# ewheel32.net
KiCad netlist of a schematic drawn in EAGLE
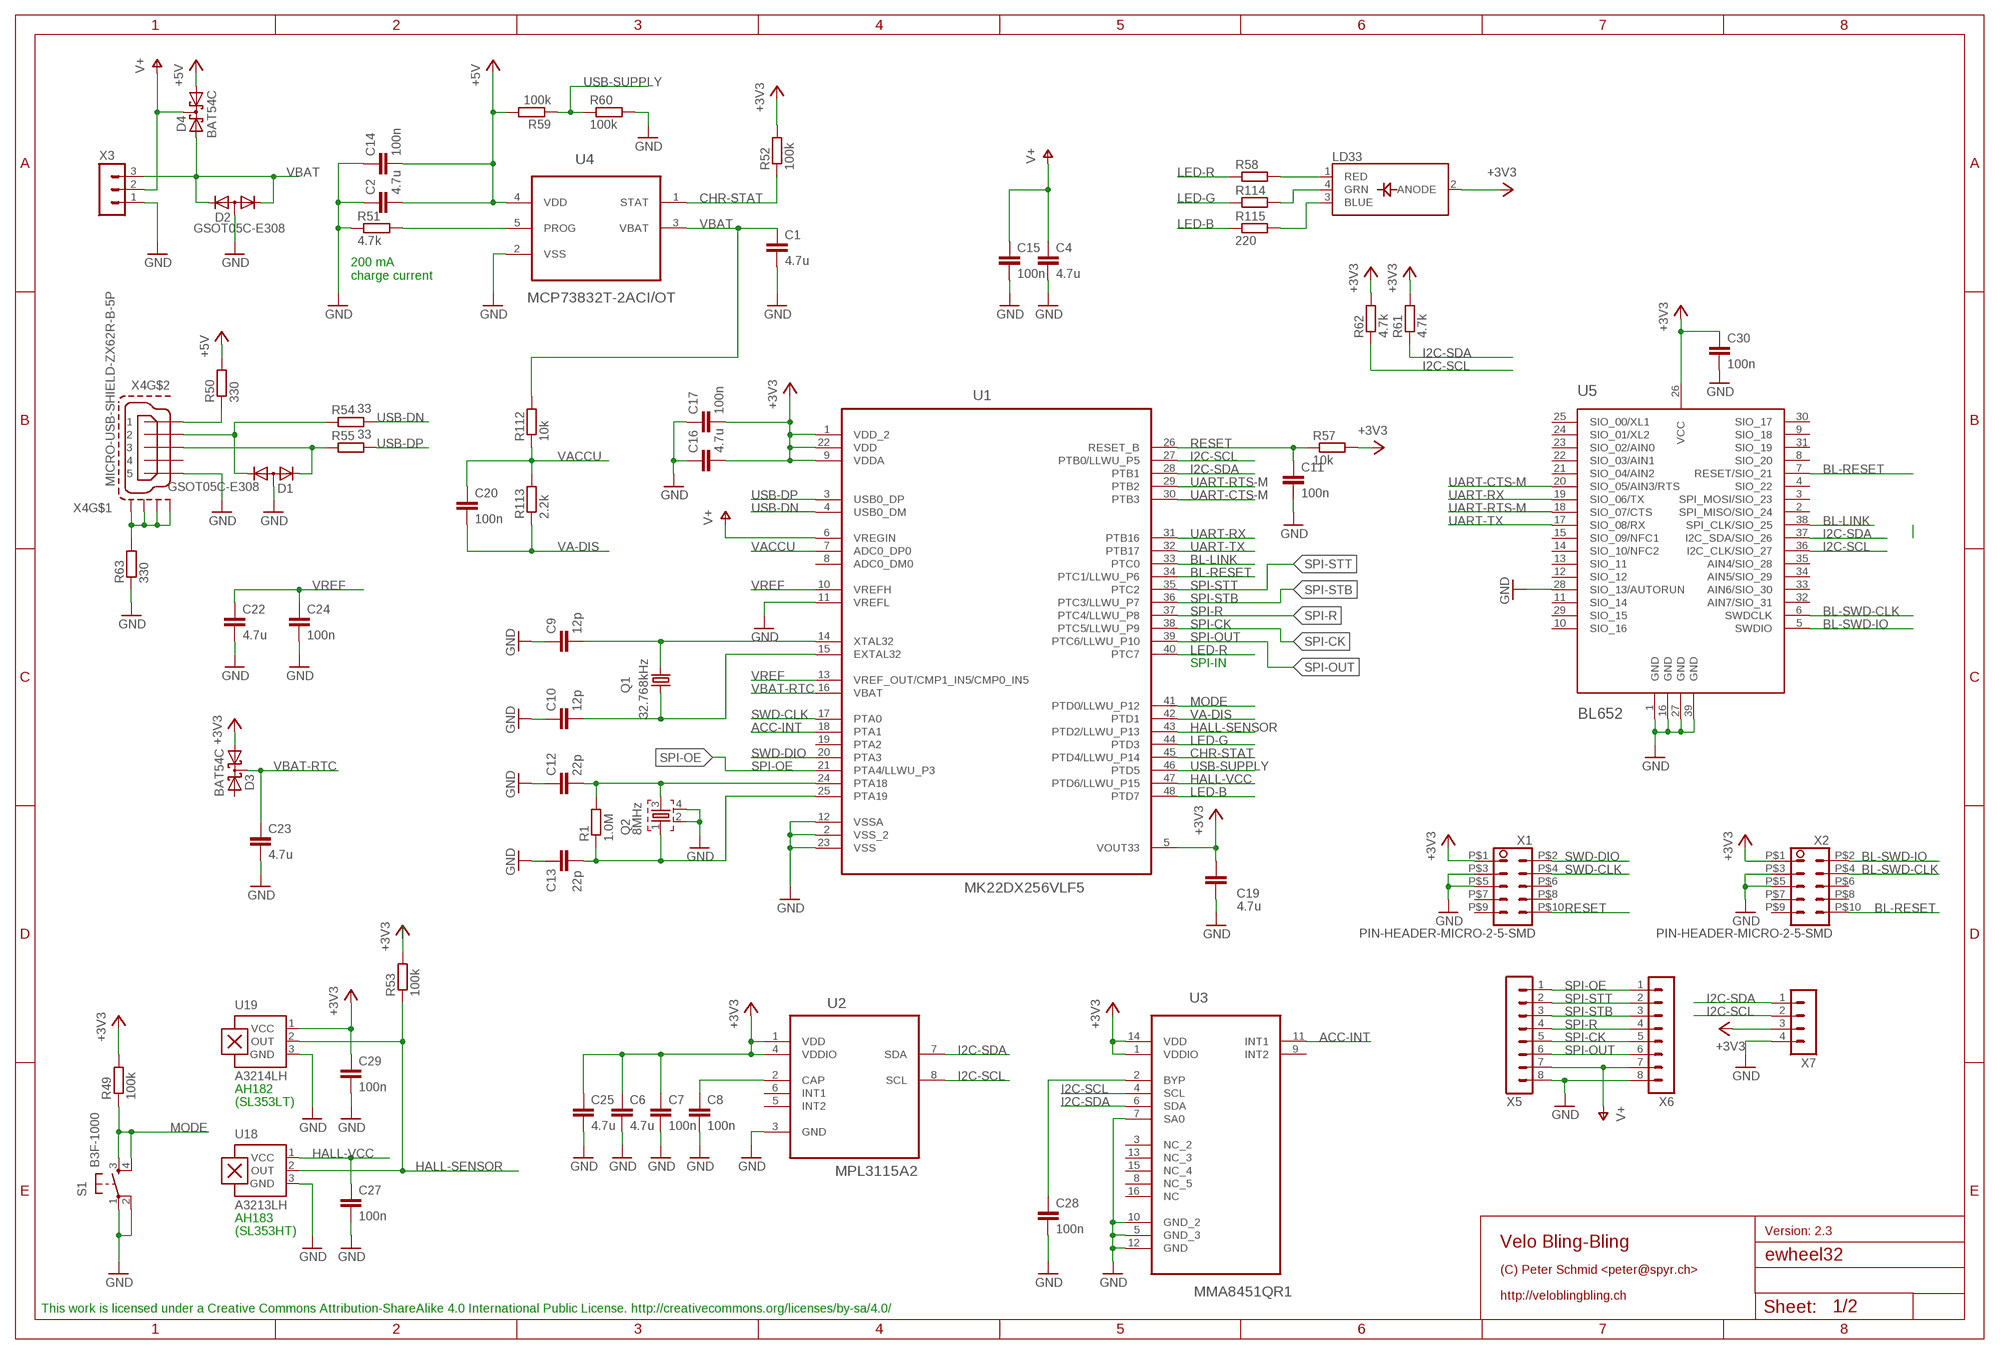
[diagram p0: schematic, sheet 1]
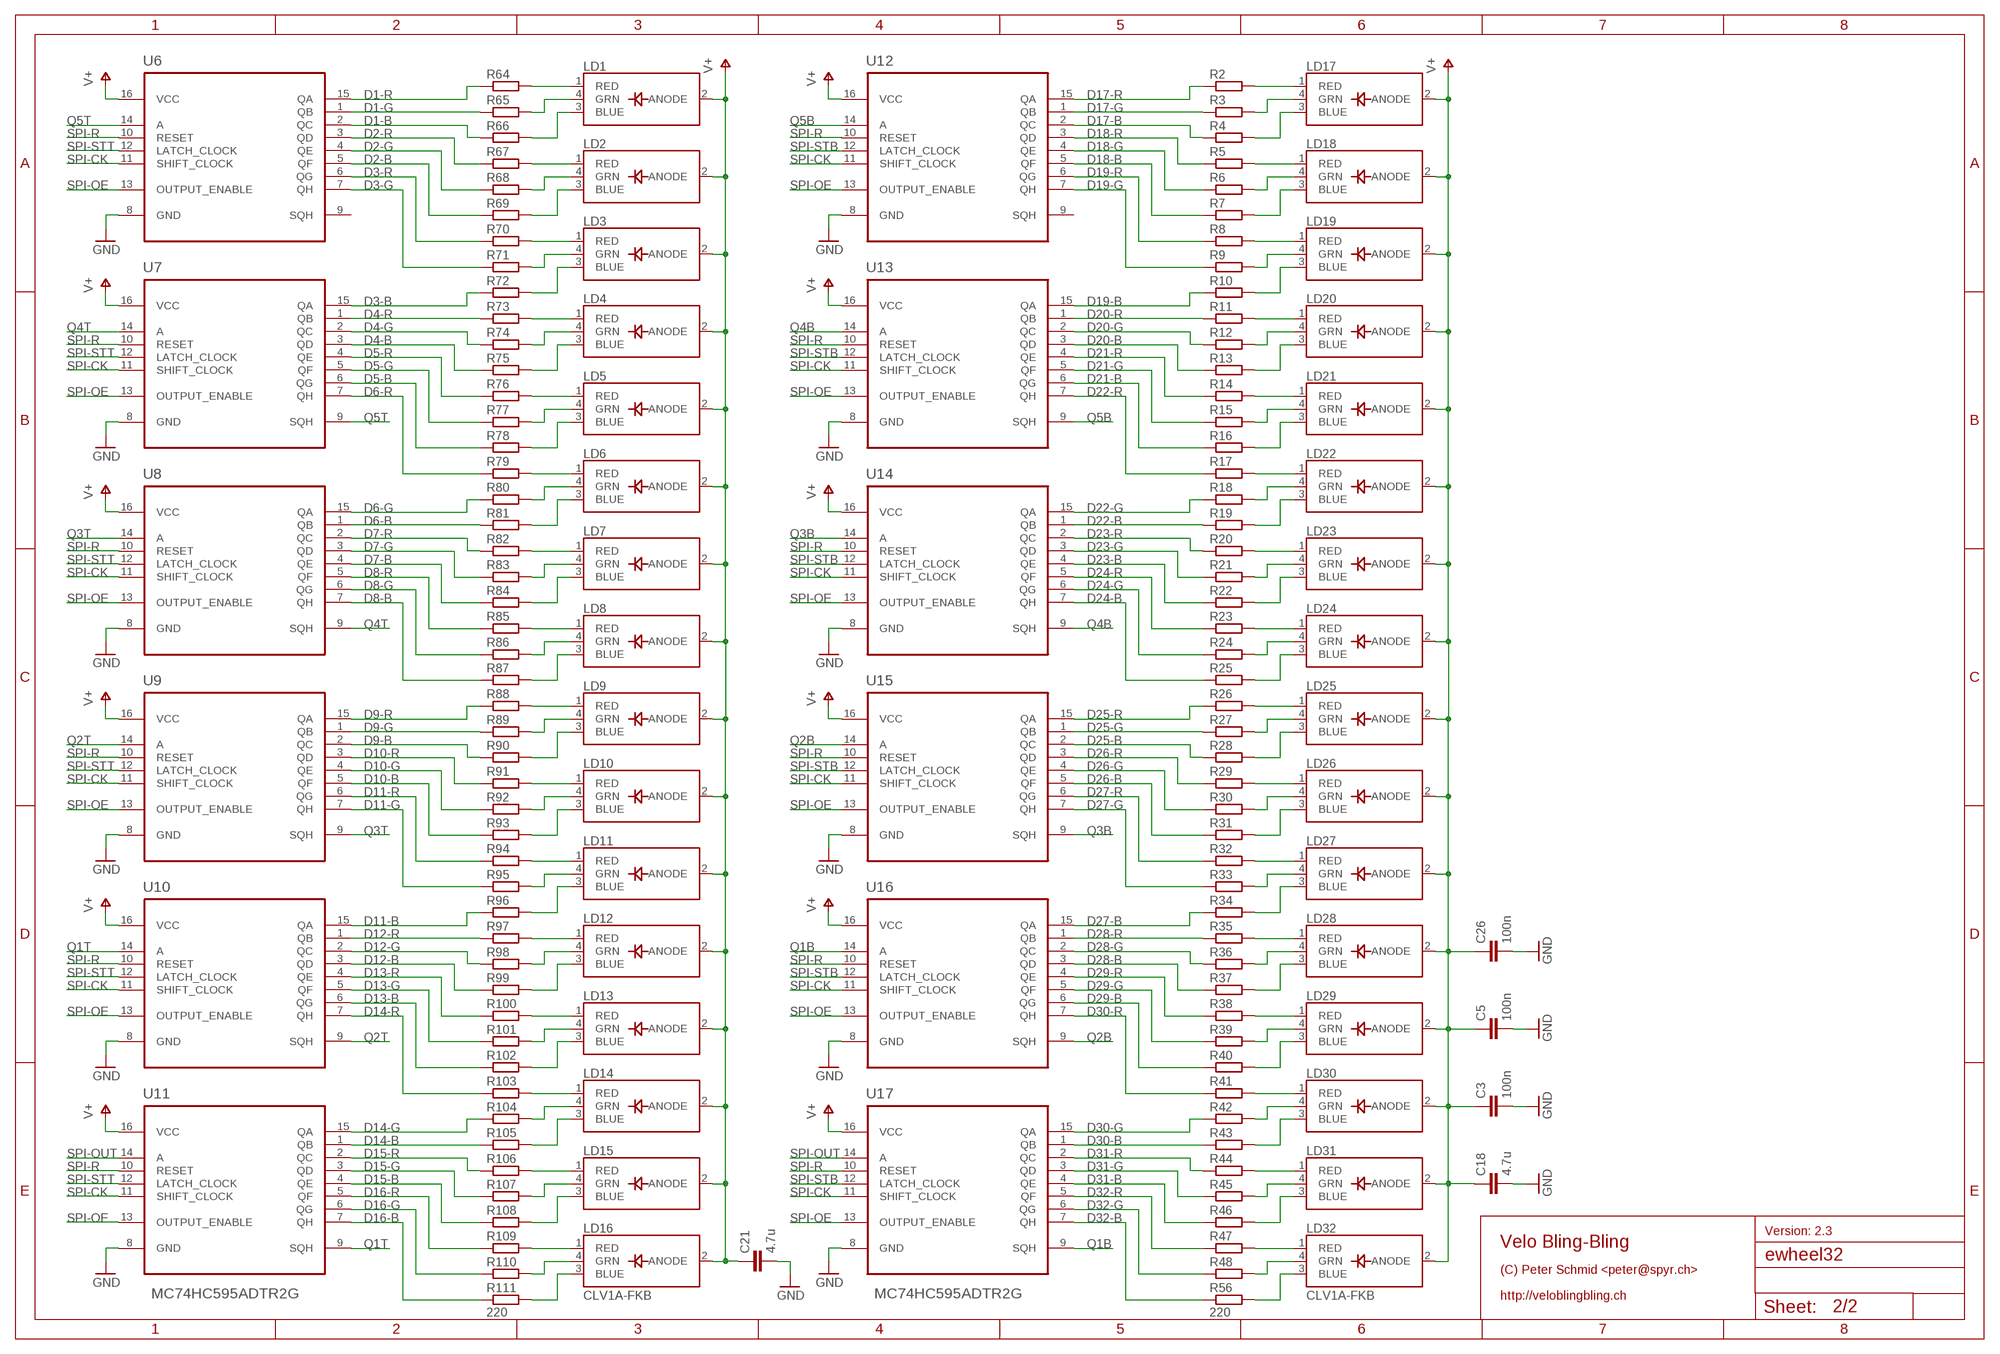
[diagram p1: schematic, sheet 2]

(export (version "E")
  (design (tool "Eeschema 10.0.6"))
  (components
    (comp (ref "C1")
      (value "4.7u")
      (footprint "eagle-import:C0805")
      (libsource (lib "eagle-import") (part "C-EUC0805"))
    )
    (comp (ref "C2")
      (value "4.7u")
      (footprint "eagle-import:C0805")
      (libsource (lib "eagle-import") (part "C-EUC0805"))
    )
    (comp (ref "C4")
      (value "4.7u")
      (footprint "eagle-import:C0805")
      (libsource (lib "eagle-import") (part "C-EUC0805"))
    )
    (comp (ref "C6")
      (value "4.7u")
      (footprint "eagle-import:C0805")
      (libsource (lib "eagle-import") (part "C-EUC0805"))
    )
    (comp (ref "C7")
      (value "100n")
      (footprint "eagle-import:C0805")
      (libsource (lib "eagle-import") (part "C-EUC0805"))
    )
    (comp (ref "C8")
      (value "100n")
      (footprint "eagle-import:C0805")
      (libsource (lib "eagle-import") (part "C-EUC0805"))
    )
    (comp (ref "C9")
      (value "12p")
      (footprint "eagle-import:C0805")
      (libsource (lib "eagle-import") (part "C-EUC0805"))
    )
    (comp (ref "C10")
      (value "12p")
      (footprint "eagle-import:C0805")
      (libsource (lib "eagle-import") (part "C-EUC0805"))
    )
    (comp (ref "C11")
      (value "100n")
      (footprint "eagle-import:C0805")
      (libsource (lib "eagle-import") (part "C-EUC0805"))
    )
    (comp (ref "C12")
      (value "22p")
      (footprint "eagle-import:C0805")
      (libsource (lib "eagle-import") (part "C-EUC0805"))
    )
    (comp (ref "C13")
      (value "22p")
      (footprint "eagle-import:C0805")
      (libsource (lib "eagle-import") (part "C-EUC0805"))
    )
    (comp (ref "C14")
      (value "100n")
      (footprint "eagle-import:C0805")
      (libsource (lib "eagle-import") (part "C-EUC0805"))
    )
    (comp (ref "C15")
      (value "100n")
      (footprint "eagle-import:C0805")
      (libsource (lib "eagle-import") (part "C-EUC0805"))
    )
    (comp (ref "C16")
      (value "4.7u")
      (footprint "eagle-import:C0805")
      (libsource (lib "eagle-import") (part "C-EUC0805"))
    )
    (comp (ref "C17")
      (value "100n")
      (footprint "eagle-import:C0805")
      (libsource (lib "eagle-import") (part "C-EUC0805"))
    )
    (comp (ref "C19")
      (value "4.7u")
      (footprint "eagle-import:C0805")
      (libsource (lib "eagle-import") (part "C-EUC0805"))
    )
    (comp (ref "C20")
      (value "100n")
      (footprint "eagle-import:C0805")
      (libsource (lib "eagle-import") (part "C-EUC0805"))
    )
    (comp (ref "C22")
      (value "4.7u")
      (footprint "eagle-import:C0805")
      (libsource (lib "eagle-import") (part "C-EUC0805"))
    )
    (comp (ref "C23")
      (value "4.7u")
      (footprint "eagle-import:C0805")
      (libsource (lib "eagle-import") (part "C-EUC0805"))
    )
    (comp (ref "C24")
      (value "100n")
      (footprint "eagle-import:C0805")
      (libsource (lib "eagle-import") (part "C-EUC0805"))
    )
    (comp (ref "C25")
      (value "4.7u")
      (footprint "eagle-import:C0805")
      (libsource (lib "eagle-import") (part "C-EUC0805"))
    )
    (comp (ref "C27")
      (value "100n")
      (footprint "eagle-import:C0805")
      (libsource (lib "eagle-import") (part "C-EUC0805"))
    )
    (comp (ref "C28")
      (value "100n")
      (footprint "eagle-import:C0805")
      (libsource (lib "eagle-import") (part "C-EUC0805"))
    )
    (comp (ref "C29")
      (value "100n")
      (footprint "eagle-import:C0805")
      (libsource (lib "eagle-import") (part "C-EUC0805"))
    )
    (comp (ref "C30")
      (value "100n")
      (footprint "eagle-import:C0805")
      (libsource (lib "eagle-import") (part "C-EUC0805"))
    )
    (comp (ref "D1")
      (value "GSOT05C-E308")
      (footprint "eagle-import:SOT23")
      (libsource (lib "eagle-import") (part "DIODE-2CA|ACSOT23"))
    )
    (comp (ref "D2")
      (value "GSOT05C-E308")
      (footprint "eagle-import:SOT23")
      (libsource (lib "eagle-import") (part "DIODE-2CA|ACSOT23"))
    )
    (comp (ref "D3")
      (value "BAT54C")
      (footprint "eagle-import:SOT23")
      (libsource (lib "eagle-import") (part "BAT54C"))
    )
    (comp (ref "D4")
      (value "BAT54C")
      (footprint "eagle-import:SOT23")
      (libsource (lib "eagle-import") (part "BAT54C"))
    )
    (comp (ref "LD33")
      (value "CLV1A-FKB")
      (footprint "eagle-import:RGBLED-PLCC4")
      (libsource (lib "eagle-import") (part "LED-RGB"))
    )
    (comp (ref "Q1")
      (value "32.768kHz")
      (footprint "eagle-import:ABS07")
      (libsource (lib "eagle-import") (part "ABS07"))
    )
    (comp (ref "Q2")
      (value "8MHz")
      (footprint "eagle-import:ABM3B")
      (libsource (lib "eagle-import") (part "ABM3B"))
    )
    (comp (ref "R1")
      (value "1.0M")
      (footprint "eagle-import:R0805")
      (libsource (lib "eagle-import") (part "R-EU_R0805"))
    )
    (comp (ref "R49")
      (value "100k")
      (footprint "eagle-import:R0805")
      (libsource (lib "eagle-import") (part "R-EU_R0805"))
    )
    (comp (ref "R50")
      (value "330")
      (footprint "eagle-import:R1206")
      (libsource (lib "eagle-import") (part "R-EU_R1206"))
    )
    (comp (ref "R51")
      (value "4.7k")
      (footprint "eagle-import:R0805")
      (libsource (lib "eagle-import") (part "R-EU_R0805"))
    )
    (comp (ref "R52")
      (value "100k")
      (footprint "eagle-import:R0805")
      (libsource (lib "eagle-import") (part "R-EU_R0805"))
    )
    (comp (ref "R53")
      (value "100k")
      (footprint "eagle-import:R0805")
      (libsource (lib "eagle-import") (part "R-EU_R0805"))
    )
    (comp (ref "R54")
      (value "33")
      (footprint "eagle-import:R0805")
      (libsource (lib "eagle-import") (part "R-EU_R0805"))
    )
    (comp (ref "R55")
      (value "33")
      (footprint "eagle-import:R0805")
      (libsource (lib "eagle-import") (part "R-EU_R0805"))
    )
    (comp (ref "R57")
      (value "10k")
      (footprint "eagle-import:R0805")
      (libsource (lib "eagle-import") (part "R-EU_R0805"))
    )
    (comp (ref "R58")
      (value "220")
      (footprint "eagle-import:R0805")
      (libsource (lib "eagle-import") (part "R-EU_R0805"))
    )
    (comp (ref "R59")
      (value "100k")
      (footprint "eagle-import:R0805")
      (libsource (lib "eagle-import") (part "R-EU_R0805"))
    )
    (comp (ref "R60")
      (value "100k")
      (footprint "eagle-import:R0805")
      (libsource (lib "eagle-import") (part "R-EU_R0805"))
    )
    (comp (ref "R61")
      (value "4.7k")
      (footprint "eagle-import:R0805")
      (libsource (lib "eagle-import") (part "R-EU_R0805"))
    )
    (comp (ref "R62")
      (value "4.7k")
      (footprint "eagle-import:R0805")
      (libsource (lib "eagle-import") (part "R-EU_R0805"))
    )
    (comp (ref "R63")
      (value "330")
      (footprint "eagle-import:R1206")
      (libsource (lib "eagle-import") (part "R-EU_R1206"))
    )
    (comp (ref "R112")
      (value "10k")
      (footprint "eagle-import:R0805")
      (libsource (lib "eagle-import") (part "R-EU_R0805"))
    )
    (comp (ref "R113")
      (value "2.2k")
      (footprint "eagle-import:R0805")
      (libsource (lib "eagle-import") (part "R-EU_R0805"))
    )
    (comp (ref "R114")
      (value "220")
      (footprint "eagle-import:R0805")
      (libsource (lib "eagle-import") (part "R-EU_R0805"))
    )
    (comp (ref "R115")
      (value "220")
      (footprint "eagle-import:R0805")
      (libsource (lib "eagle-import") (part "R-EU_R0805"))
    )
    (comp (ref "S1")
      (value "B3F-1000")
      (footprint "eagle-import:B3S-1000")
      (libsource (lib "eagle-import") (part "B3S-1000"))
    )
    (comp (ref "U1")
      (value "MK22DX256VLF5")
      (footprint "eagle-import:QFP50P900X900X160-48N")
      (fields (field (name "MPN") "MK20DX128VLF5"))
      (libsource (lib "eagle-import") (part "MK20DX128VLF5"))
    )
    (comp (ref "U2")
      (value "MPL3115A2")
      (footprint "eagle-import:DFN300X500X120-8N")
      (libsource (lib "eagle-import") (part "MPL3115A2"))
    )
    (comp (ref "U3")
      (value "MMA8451QR1")
      (footprint "eagle-import:QFN50P300X300X100-16N")
      (libsource (lib "eagle-import") (part "MMA8451QR1"))
    )
    (comp (ref "U4")
      (value "MCP73832T-2ACI/OT")
      (footprint "eagle-import:SOT95P280X145-5N")
      (fields (field (name "MPN") "MCP73831T-2ACI/OT"))
      (libsource (lib "eagle-import") (part "MCP73831T-2ACI/OT"))
    )
    (comp (ref "U5")
      (value "BL652")
      (footprint "eagle-import:BL652")
      (libsource (lib "eagle-import") (part "LAIRD_BL652"))
    )
    (comp (ref "U18")
      (value "A3213LH")
      (footprint "eagle-import:SOT23-W")
      (fields (field (name "MPN") "A1381LLHLT-T"))
      (libsource (lib "eagle-import") (part "A13?LH81"))
    )
    (comp (ref "U19")
      (value "A3214LH")
      (footprint "eagle-import:SOT23-W")
      (fields (field (name "MPN") "A1381LLHLT-T"))
      (libsource (lib "eagle-import") (part "A13?LH81"))
    )
    (comp (ref "X1")
      (value "PIN-HEADER-MICRO-2-5-SMD")
      (footprint "eagle-import:PIN-HEADER-NICRO-2-5-SMD")
      (libsource (lib "eagle-import") (part "PIN-HEADER-MICRO-2-5-SMD"))
    )
    (comp (ref "X2")
      (value "PIN-HEADER-MICRO-2-5-SMD")
      (footprint "eagle-import:PIN-HEADER-NICRO-2-5-SMD")
      (libsource (lib "eagle-import") (part "PIN-HEADER-MICRO-2-5-SMD"))
    )
    (comp (ref "X3")
      (value "MA03-1")
      (footprint "eagle-import:MA03-1")
      (libsource (lib "eagle-import") (part "MA03-1"))
    )
    (comp (ref "X4")
      (value "MICRO-USB-SHIELD-ZX62R-B-5P")
      (footprint "eagle-import:ZX62R-B-5P")
      (libsource (lib "eagle-import") (part "MICRO-USB-SHIELD-ZX62R-B-5P"))
    )
    (comp (ref "X5")
      (value "MA08-1")
      (footprint "eagle-import:MA08-1")
      (libsource (lib "eagle-import") (part "MA08-1"))
    )
    (comp (ref "X6")
      (value "MA08-1")
      (footprint "eagle-import:MA08-1")
      (libsource (lib "eagle-import") (part "MA08-1"))
    )
    (comp (ref "X7")
      (value "MA04-1")
      (footprint "eagle-import:MA04-1")
      (libsource (lib "eagle-import") (part "MA04-1"))
    )
    (comp (ref "C3")
      (value "100n")
      (footprint "eagle-import:C0805")
      (libsource (lib "eagle-import") (part "C-EUC0805"))
    )
    (comp (ref "C5")
      (value "100n")
      (footprint "eagle-import:C0805")
      (libsource (lib "eagle-import") (part "C-EUC0805"))
    )
    (comp (ref "C18")
      (value "4.7u")
      (footprint "eagle-import:C0805")
      (libsource (lib "eagle-import") (part "C-EUC0805"))
    )
    (comp (ref "C21")
      (value "4.7u")
      (footprint "eagle-import:C0805")
      (libsource (lib "eagle-import") (part "C-EUC0805"))
    )
    (comp (ref "C26")
      (value "100n")
      (footprint "eagle-import:C0805")
      (libsource (lib "eagle-import") (part "C-EUC0805"))
    )
    (comp (ref "LD1")
      (value "CLV1A-FKB")
      (footprint "eagle-import:RGBLED-PLCC4")
      (libsource (lib "eagle-import") (part "LED-RGB"))
    )
    (comp (ref "LD2")
      (value "CLV1A-FKB")
      (footprint "eagle-import:RGBLED-PLCC4")
      (libsource (lib "eagle-import") (part "LED-RGB"))
    )
    (comp (ref "LD3")
      (value "CLV1A-FKB")
      (footprint "eagle-import:RGBLED-PLCC4")
      (libsource (lib "eagle-import") (part "LED-RGB"))
    )
    (comp (ref "LD4")
      (value "CLV1A-FKB")
      (footprint "eagle-import:RGBLED-PLCC4")
      (libsource (lib "eagle-import") (part "LED-RGB"))
    )
    (comp (ref "LD5")
      (value "CLV1A-FKB")
      (footprint "eagle-import:RGBLED-PLCC4")
      (libsource (lib "eagle-import") (part "LED-RGB"))
    )
    (comp (ref "LD6")
      (value "CLV1A-FKB")
      (footprint "eagle-import:RGBLED-PLCC4")
      (libsource (lib "eagle-import") (part "LED-RGB"))
    )
    (comp (ref "LD7")
      (value "CLV1A-FKB")
      (footprint "eagle-import:RGBLED-PLCC4")
      (libsource (lib "eagle-import") (part "LED-RGB"))
    )
    (comp (ref "LD8")
      (value "CLV1A-FKB")
      (footprint "eagle-import:RGBLED-PLCC4")
      (libsource (lib "eagle-import") (part "LED-RGB"))
    )
    (comp (ref "LD9")
      (value "CLV1A-FKB")
      (footprint "eagle-import:RGBLED-PLCC4")
      (libsource (lib "eagle-import") (part "LED-RGB"))
    )
    (comp (ref "LD10")
      (value "CLV1A-FKB")
      (footprint "eagle-import:RGBLED-PLCC4")
      (libsource (lib "eagle-import") (part "LED-RGB"))
    )
    (comp (ref "LD11")
      (value "CLV1A-FKB")
      (footprint "eagle-import:RGBLED-PLCC4")
      (libsource (lib "eagle-import") (part "LED-RGB"))
    )
    (comp (ref "LD12")
      (value "CLV1A-FKB")
      (footprint "eagle-import:RGBLED-PLCC4")
      (libsource (lib "eagle-import") (part "LED-RGB"))
    )
    (comp (ref "LD13")
      (value "CLV1A-FKB")
      (footprint "eagle-import:RGBLED-PLCC4")
      (libsource (lib "eagle-import") (part "LED-RGB"))
    )
    (comp (ref "LD14")
      (value "CLV1A-FKB")
      (footprint "eagle-import:RGBLED-PLCC4")
      (libsource (lib "eagle-import") (part "LED-RGB"))
    )
    (comp (ref "LD15")
      (value "CLV1A-FKB")
      (footprint "eagle-import:RGBLED-PLCC4")
      (libsource (lib "eagle-import") (part "LED-RGB"))
    )
    (comp (ref "LD16")
      (value "CLV1A-FKB")
      (footprint "eagle-import:RGBLED-PLCC4")
      (libsource (lib "eagle-import") (part "LED-RGB"))
    )
    (comp (ref "LD17")
      (value "CLV1A-FKB")
      (footprint "eagle-import:RGBLED-PLCC4")
      (libsource (lib "eagle-import") (part "LED-RGB"))
    )
    (comp (ref "LD18")
      (value "CLV1A-FKB")
      (footprint "eagle-import:RGBLED-PLCC4")
      (libsource (lib "eagle-import") (part "LED-RGB"))
    )
    (comp (ref "LD19")
      (value "CLV1A-FKB")
      (footprint "eagle-import:RGBLED-PLCC4")
      (libsource (lib "eagle-import") (part "LED-RGB"))
    )
    (comp (ref "LD20")
      (value "CLV1A-FKB")
      (footprint "eagle-import:RGBLED-PLCC4")
      (libsource (lib "eagle-import") (part "LED-RGB"))
    )
    (comp (ref "LD21")
      (value "CLV1A-FKB")
      (footprint "eagle-import:RGBLED-PLCC4")
      (libsource (lib "eagle-import") (part "LED-RGB"))
    )
    (comp (ref "LD22")
      (value "CLV1A-FKB")
      (footprint "eagle-import:RGBLED-PLCC4")
      (libsource (lib "eagle-import") (part "LED-RGB"))
    )
    (comp (ref "LD23")
      (value "CLV1A-FKB")
      (footprint "eagle-import:RGBLED-PLCC4")
      (libsource (lib "eagle-import") (part "LED-RGB"))
    )
    (comp (ref "LD24")
      (value "CLV1A-FKB")
      (footprint "eagle-import:RGBLED-PLCC4")
      (libsource (lib "eagle-import") (part "LED-RGB"))
    )
    (comp (ref "LD25")
      (value "CLV1A-FKB")
      (footprint "eagle-import:RGBLED-PLCC4")
      (libsource (lib "eagle-import") (part "LED-RGB"))
    )
    (comp (ref "LD26")
      (value "CLV1A-FKB")
      (footprint "eagle-import:RGBLED-PLCC4")
      (libsource (lib "eagle-import") (part "LED-RGB"))
    )
    (comp (ref "LD27")
      (value "CLV1A-FKB")
      (footprint "eagle-import:RGBLED-PLCC4")
      (libsource (lib "eagle-import") (part "LED-RGB"))
    )
    (comp (ref "LD28")
      (value "CLV1A-FKB")
      (footprint "eagle-import:RGBLED-PLCC4")
      (libsource (lib "eagle-import") (part "LED-RGB"))
    )
    (comp (ref "LD29")
      (value "CLV1A-FKB")
      (footprint "eagle-import:RGBLED-PLCC4")
      (libsource (lib "eagle-import") (part "LED-RGB"))
    )
    (comp (ref "LD30")
      (value "CLV1A-FKB")
      (footprint "eagle-import:RGBLED-PLCC4")
      (libsource (lib "eagle-import") (part "LED-RGB"))
    )
    (comp (ref "LD31")
      (value "CLV1A-FKB")
      (footprint "eagle-import:RGBLED-PLCC4")
      (libsource (lib "eagle-import") (part "LED-RGB"))
    )
    (comp (ref "LD32")
      (value "CLV1A-FKB")
      (footprint "eagle-import:RGBLED-PLCC4")
      (libsource (lib "eagle-import") (part "LED-RGB"))
    )
    (comp (ref "R2")
      (value "220")
      (footprint "eagle-import:R0805")
      (libsource (lib "eagle-import") (part "R-EU_R0805"))
    )
    (comp (ref "R3")
      (value "220")
      (footprint "eagle-import:R0805")
      (libsource (lib "eagle-import") (part "R-EU_R0805"))
    )
    (comp (ref "R4")
      (value "220")
      (footprint "eagle-import:R0805")
      (libsource (lib "eagle-import") (part "R-EU_R0805"))
    )
    (comp (ref "R5")
      (value "220")
      (footprint "eagle-import:R0805")
      (libsource (lib "eagle-import") (part "R-EU_R0805"))
    )
    (comp (ref "R6")
      (value "220")
      (footprint "eagle-import:R0805")
      (libsource (lib "eagle-import") (part "R-EU_R0805"))
    )
    (comp (ref "R7")
      (value "220")
      (footprint "eagle-import:R0805")
      (libsource (lib "eagle-import") (part "R-EU_R0805"))
    )
    (comp (ref "R8")
      (value "220")
      (footprint "eagle-import:R0805")
      (libsource (lib "eagle-import") (part "R-EU_R0805"))
    )
    (comp (ref "R9")
      (value "220")
      (footprint "eagle-import:R0805")
      (libsource (lib "eagle-import") (part "R-EU_R0805"))
    )
    (comp (ref "R10")
      (value "220")
      (footprint "eagle-import:R0805")
      (libsource (lib "eagle-import") (part "R-EU_R0805"))
    )
    (comp (ref "R11")
      (value "220")
      (footprint "eagle-import:R0805")
      (libsource (lib "eagle-import") (part "R-EU_R0805"))
    )
    (comp (ref "R12")
      (value "220")
      (footprint "eagle-import:R0805")
      (libsource (lib "eagle-import") (part "R-EU_R0805"))
    )
    (comp (ref "R13")
      (value "220")
      (footprint "eagle-import:R0805")
      (libsource (lib "eagle-import") (part "R-EU_R0805"))
    )
    (comp (ref "R14")
      (value "220")
      (footprint "eagle-import:R0805")
      (libsource (lib "eagle-import") (part "R-EU_R0805"))
    )
    (comp (ref "R15")
      (value "220")
      (footprint "eagle-import:R0805")
      (libsource (lib "eagle-import") (part "R-EU_R0805"))
    )
    (comp (ref "R16")
      (value "220")
      (footprint "eagle-import:R0805")
      (libsource (lib "eagle-import") (part "R-EU_R0805"))
    )
    (comp (ref "R17")
      (value "220")
      (footprint "eagle-import:R0805")
      (libsource (lib "eagle-import") (part "R-EU_R0805"))
    )
    (comp (ref "R18")
      (value "220")
      (footprint "eagle-import:R0805")
      (libsource (lib "eagle-import") (part "R-EU_R0805"))
    )
    (comp (ref "R19")
      (value "220")
      (footprint "eagle-import:R0805")
      (libsource (lib "eagle-import") (part "R-EU_R0805"))
    )
    (comp (ref "R20")
      (value "220")
      (footprint "eagle-import:R0805")
      (libsource (lib "eagle-import") (part "R-EU_R0805"))
    )
    (comp (ref "R21")
      (value "220")
      (footprint "eagle-import:R0805")
      (libsource (lib "eagle-import") (part "R-EU_R0805"))
    )
    (comp (ref "R22")
      (value "220")
      (footprint "eagle-import:R0805")
      (libsource (lib "eagle-import") (part "R-EU_R0805"))
    )
    (comp (ref "R23")
      (value "220")
      (footprint "eagle-import:R0805")
      (libsource (lib "eagle-import") (part "R-EU_R0805"))
    )
    (comp (ref "R24")
      (value "220")
      (footprint "eagle-import:R0805")
      (libsource (lib "eagle-import") (part "R-EU_R0805"))
    )
    (comp (ref "R25")
      (value "220")
      (footprint "eagle-import:R0805")
      (libsource (lib "eagle-import") (part "R-EU_R0805"))
    )
    (comp (ref "R26")
      (value "220")
      (footprint "eagle-import:R0805")
      (libsource (lib "eagle-import") (part "R-EU_R0805"))
    )
    (comp (ref "R27")
      (value "220")
      (footprint "eagle-import:R0805")
      (libsource (lib "eagle-import") (part "R-EU_R0805"))
    )
    (comp (ref "R28")
      (value "220")
      (footprint "eagle-import:R0805")
      (libsource (lib "eagle-import") (part "R-EU_R0805"))
    )
    (comp (ref "R29")
      (value "220")
      (footprint "eagle-import:R0805")
      (libsource (lib "eagle-import") (part "R-EU_R0805"))
    )
    (comp (ref "R30")
      (value "220")
      (footprint "eagle-import:R0805")
      (libsource (lib "eagle-import") (part "R-EU_R0805"))
    )
    (comp (ref "R31")
      (value "220")
      (footprint "eagle-import:R0805")
      (libsource (lib "eagle-import") (part "R-EU_R0805"))
    )
    (comp (ref "R32")
      (value "220")
      (footprint "eagle-import:R0805")
      (libsource (lib "eagle-import") (part "R-EU_R0805"))
    )
    (comp (ref "R33")
      (value "220")
      (footprint "eagle-import:R0805")
      (libsource (lib "eagle-import") (part "R-EU_R0805"))
    )
    (comp (ref "R34")
      (value "220")
      (footprint "eagle-import:R0805")
      (libsource (lib "eagle-import") (part "R-EU_R0805"))
    )
    (comp (ref "R35")
      (value "220")
      (footprint "eagle-import:R0805")
      (libsource (lib "eagle-import") (part "R-EU_R0805"))
    )
    (comp (ref "R36")
      (value "220")
      (footprint "eagle-import:R0805")
      (libsource (lib "eagle-import") (part "R-EU_R0805"))
    )
    (comp (ref "R37")
      (value "220")
      (footprint "eagle-import:R0805")
      (libsource (lib "eagle-import") (part "R-EU_R0805"))
    )
    (comp (ref "R38")
      (value "220")
      (footprint "eagle-import:R0805")
      (libsource (lib "eagle-import") (part "R-EU_R0805"))
    )
    (comp (ref "R39")
      (value "220")
      (footprint "eagle-import:R0805")
      (libsource (lib "eagle-import") (part "R-EU_R0805"))
    )
    (comp (ref "R40")
      (value "220")
      (footprint "eagle-import:R0805")
      (libsource (lib "eagle-import") (part "R-EU_R0805"))
    )
    (comp (ref "R41")
      (value "220")
      (footprint "eagle-import:R0805")
      (libsource (lib "eagle-import") (part "R-EU_R0805"))
    )
    (comp (ref "R42")
      (value "220")
      (footprint "eagle-import:R0805")
      (libsource (lib "eagle-import") (part "R-EU_R0805"))
    )
    (comp (ref "R43")
      (value "220")
      (footprint "eagle-import:R0805")
      (libsource (lib "eagle-import") (part "R-EU_R0805"))
    )
    (comp (ref "R44")
      (value "220")
      (footprint "eagle-import:R0805")
      (libsource (lib "eagle-import") (part "R-EU_R0805"))
    )
    (comp (ref "R45")
      (value "220")
      (footprint "eagle-import:R0805")
      (libsource (lib "eagle-import") (part "R-EU_R0805"))
    )
    (comp (ref "R46")
      (value "220")
      (footprint "eagle-import:R0805")
      (libsource (lib "eagle-import") (part "R-EU_R0805"))
    )
    (comp (ref "R47")
      (value "220")
      (footprint "eagle-import:R0805")
      (libsource (lib "eagle-import") (part "R-EU_R0805"))
    )
    (comp (ref "R48")
      (value "220")
      (footprint "eagle-import:R0805")
      (libsource (lib "eagle-import") (part "R-EU_R0805"))
    )
    (comp (ref "R56")
      (value "220")
      (footprint "eagle-import:R0805")
      (libsource (lib "eagle-import") (part "R-EU_R0805"))
    )
    (comp (ref "R64")
      (value "220")
      (footprint "eagle-import:R0805")
      (libsource (lib "eagle-import") (part "R-EU_R0805"))
    )
    (comp (ref "R65")
      (value "220")
      (footprint "eagle-import:R0805")
      (libsource (lib "eagle-import") (part "R-EU_R0805"))
    )
    (comp (ref "R66")
      (value "220")
      (footprint "eagle-import:R0805")
      (libsource (lib "eagle-import") (part "R-EU_R0805"))
    )
    (comp (ref "R67")
      (value "220")
      (footprint "eagle-import:R0805")
      (libsource (lib "eagle-import") (part "R-EU_R0805"))
    )
    (comp (ref "R68")
      (value "220")
      (footprint "eagle-import:R0805")
      (libsource (lib "eagle-import") (part "R-EU_R0805"))
    )
    (comp (ref "R69")
      (value "220")
      (footprint "eagle-import:R0805")
      (libsource (lib "eagle-import") (part "R-EU_R0805"))
    )
    (comp (ref "R70")
      (value "220")
      (footprint "eagle-import:R0805")
      (libsource (lib "eagle-import") (part "R-EU_R0805"))
    )
    (comp (ref "R71")
      (value "220")
      (footprint "eagle-import:R0805")
      (libsource (lib "eagle-import") (part "R-EU_R0805"))
    )
    (comp (ref "R72")
      (value "220")
      (footprint "eagle-import:R0805")
      (libsource (lib "eagle-import") (part "R-EU_R0805"))
    )
    (comp (ref "R73")
      (value "220")
      (footprint "eagle-import:R0805")
      (libsource (lib "eagle-import") (part "R-EU_R0805"))
    )
    (comp (ref "R74")
      (value "220")
      (footprint "eagle-import:R0805")
      (libsource (lib "eagle-import") (part "R-EU_R0805"))
    )
    (comp (ref "R75")
      (value "220")
      (footprint "eagle-import:R0805")
      (libsource (lib "eagle-import") (part "R-EU_R0805"))
    )
    (comp (ref "R76")
      (value "220")
      (footprint "eagle-import:R0805")
      (libsource (lib "eagle-import") (part "R-EU_R0805"))
    )
    (comp (ref "R77")
      (value "220")
      (footprint "eagle-import:R0805")
      (libsource (lib "eagle-import") (part "R-EU_R0805"))
    )
    (comp (ref "R78")
      (value "220")
      (footprint "eagle-import:R0805")
      (libsource (lib "eagle-import") (part "R-EU_R0805"))
    )
    (comp (ref "R79")
      (value "220")
      (footprint "eagle-import:R0805")
      (libsource (lib "eagle-import") (part "R-EU_R0805"))
    )
    (comp (ref "R80")
      (value "220")
      (footprint "eagle-import:R0805")
      (libsource (lib "eagle-import") (part "R-EU_R0805"))
    )
    (comp (ref "R81")
      (value "220")
      (footprint "eagle-import:R0805")
      (libsource (lib "eagle-import") (part "R-EU_R0805"))
    )
    (comp (ref "R82")
      (value "220")
      (footprint "eagle-import:R0805")
      (libsource (lib "eagle-import") (part "R-EU_R0805"))
    )
    (comp (ref "R83")
      (value "220")
      (footprint "eagle-import:R0805")
      (libsource (lib "eagle-import") (part "R-EU_R0805"))
    )
    (comp (ref "R84")
      (value "220")
      (footprint "eagle-import:R0805")
      (libsource (lib "eagle-import") (part "R-EU_R0805"))
    )
    (comp (ref "R85")
      (value "220")
      (footprint "eagle-import:R0805")
      (libsource (lib "eagle-import") (part "R-EU_R0805"))
    )
    (comp (ref "R86")
      (value "220")
      (footprint "eagle-import:R0805")
      (libsource (lib "eagle-import") (part "R-EU_R0805"))
    )
    (comp (ref "R87")
      (value "220")
      (footprint "eagle-import:R0805")
      (libsource (lib "eagle-import") (part "R-EU_R0805"))
    )
    (comp (ref "R88")
      (value "220")
      (footprint "eagle-import:R0805")
      (libsource (lib "eagle-import") (part "R-EU_R0805"))
    )
    (comp (ref "R89")
      (value "220")
      (footprint "eagle-import:R0805")
      (libsource (lib "eagle-import") (part "R-EU_R0805"))
    )
    (comp (ref "R90")
      (value "220")
      (footprint "eagle-import:R0805")
      (libsource (lib "eagle-import") (part "R-EU_R0805"))
    )
    (comp (ref "R91")
      (value "220")
      (footprint "eagle-import:R0805")
      (libsource (lib "eagle-import") (part "R-EU_R0805"))
    )
    (comp (ref "R92")
      (value "220")
      (footprint "eagle-import:R0805")
      (libsource (lib "eagle-import") (part "R-EU_R0805"))
    )
    (comp (ref "R93")
      (value "220")
      (footprint "eagle-import:R0805")
      (libsource (lib "eagle-import") (part "R-EU_R0805"))
    )
    (comp (ref "R94")
      (value "220")
      (footprint "eagle-import:R0805")
      (libsource (lib "eagle-import") (part "R-EU_R0805"))
    )
    (comp (ref "R95")
      (value "220")
      (footprint "eagle-import:R0805")
      (libsource (lib "eagle-import") (part "R-EU_R0805"))
    )
    (comp (ref "R96")
      (value "220")
      (footprint "eagle-import:R0805")
      (libsource (lib "eagle-import") (part "R-EU_R0805"))
    )
    (comp (ref "R97")
      (value "220")
      (footprint "eagle-import:R0805")
      (libsource (lib "eagle-import") (part "R-EU_R0805"))
    )
    (comp (ref "R98")
      (value "220")
      (footprint "eagle-import:R0805")
      (libsource (lib "eagle-import") (part "R-EU_R0805"))
    )
    (comp (ref "R99")
      (value "220")
      (footprint "eagle-import:R0805")
      (libsource (lib "eagle-import") (part "R-EU_R0805"))
    )
    (comp (ref "R100")
      (value "220")
      (footprint "eagle-import:R0805")
      (libsource (lib "eagle-import") (part "R-EU_R0805"))
    )
    (comp (ref "R101")
      (value "220")
      (footprint "eagle-import:R0805")
      (libsource (lib "eagle-import") (part "R-EU_R0805"))
    )
    (comp (ref "R102")
      (value "220")
      (footprint "eagle-import:R0805")
      (libsource (lib "eagle-import") (part "R-EU_R0805"))
    )
    (comp (ref "R103")
      (value "220")
      (footprint "eagle-import:R0805")
      (libsource (lib "eagle-import") (part "R-EU_R0805"))
    )
    (comp (ref "R104")
      (value "220")
      (footprint "eagle-import:R0805")
      (libsource (lib "eagle-import") (part "R-EU_R0805"))
    )
    (comp (ref "R105")
      (value "220")
      (footprint "eagle-import:R0805")
      (libsource (lib "eagle-import") (part "R-EU_R0805"))
    )
    (comp (ref "R106")
      (value "220")
      (footprint "eagle-import:R0805")
      (libsource (lib "eagle-import") (part "R-EU_R0805"))
    )
    (comp (ref "R107")
      (value "220")
      (footprint "eagle-import:R0805")
      (libsource (lib "eagle-import") (part "R-EU_R0805"))
    )
    (comp (ref "R108")
      (value "220")
      (footprint "eagle-import:R0805")
      (libsource (lib "eagle-import") (part "R-EU_R0805"))
    )
    (comp (ref "R109")
      (value "220")
      (footprint "eagle-import:R0805")
      (libsource (lib "eagle-import") (part "R-EU_R0805"))
    )
    (comp (ref "R110")
      (value "220")
      (footprint "eagle-import:R0805")
      (libsource (lib "eagle-import") (part "R-EU_R0805"))
    )
    (comp (ref "R111")
      (value "220")
      (footprint "eagle-import:R0805")
      (libsource (lib "eagle-import") (part "R-EU_R0805"))
    )
    (comp (ref "U6")
      (value "MC74HC595ADTR2G")
      (footprint "eagle-import:SOP65P640X120-16N")
      (libsource (lib "eagle-import") (part "MC74HC595ADTR2G"))
    )
    (comp (ref "U7")
      (value "MC74HC595ADTR2G")
      (footprint "eagle-import:SOP65P640X120-16N")
      (libsource (lib "eagle-import") (part "MC74HC595ADTR2G"))
    )
    (comp (ref "U8")
      (value "MC74HC595ADTR2G")
      (footprint "eagle-import:SOP65P640X120-16N")
      (libsource (lib "eagle-import") (part "MC74HC595ADTR2G"))
    )
    (comp (ref "U9")
      (value "MC74HC595ADTR2G")
      (footprint "eagle-import:SOP65P640X120-16N")
      (libsource (lib "eagle-import") (part "MC74HC595ADTR2G"))
    )
    (comp (ref "U10")
      (value "MC74HC595ADTR2G")
      (footprint "eagle-import:SOP65P640X120-16N")
      (libsource (lib "eagle-import") (part "MC74HC595ADTR2G"))
    )
    (comp (ref "U11")
      (value "MC74HC595ADTR2G")
      (footprint "eagle-import:SOP65P640X120-16N")
      (libsource (lib "eagle-import") (part "MC74HC595ADTR2G"))
    )
    (comp (ref "U12")
      (value "MC74HC595ADTR2G")
      (footprint "eagle-import:SOP65P640X120-16N")
      (libsource (lib "eagle-import") (part "MC74HC595ADTR2G"))
    )
    (comp (ref "U13")
      (value "MC74HC595ADTR2G")
      (footprint "eagle-import:SOP65P640X120-16N")
      (libsource (lib "eagle-import") (part "MC74HC595ADTR2G"))
    )
    (comp (ref "U14")
      (value "MC74HC595ADTR2G")
      (footprint "eagle-import:SOP65P640X120-16N")
      (libsource (lib "eagle-import") (part "MC74HC595ADTR2G"))
    )
    (comp (ref "U15")
      (value "MC74HC595ADTR2G")
      (footprint "eagle-import:SOP65P640X120-16N")
      (libsource (lib "eagle-import") (part "MC74HC595ADTR2G"))
    )
    (comp (ref "U16")
      (value "MC74HC595ADTR2G")
      (footprint "eagle-import:SOP65P640X120-16N")
      (libsource (lib "eagle-import") (part "MC74HC595ADTR2G"))
    )
    (comp (ref "U17")
      (value "MC74HC595ADTR2G")
      (footprint "eagle-import:SOP65P640X120-16N")
      (libsource (lib "eagle-import") (part "MC74HC595ADTR2G"))
    )
  )
  (nets
    (net (code "1") (name "+3V3") (class "Default")
      (node (ref "C16") (pin "2") (pinfunction "2_2") (pintype "passive"))
      (node (ref "C17") (pin "2") (pinfunction "2_2") (pintype "passive"))
      (node (ref "C19") (pin "1") (pinfunction "1_1") (pintype "passive"))
      (node (ref "C25") (pin "1") (pinfunction "1_1") (pintype "passive"))
      (node (ref "C29") (pin "1") (pinfunction "1_1") (pintype "passive"))
      (node (ref "C30") (pin "1") (pinfunction "1_1") (pintype "passive"))
      (node (ref "C6") (pin "1") (pinfunction "1_1") (pintype "passive"))
      (node (ref "C7") (pin "1") (pinfunction "1_1") (pintype "passive"))
      (node (ref "D3") (pin "1") (pinfunction "A1_1") (pintype "passive"))
      (node (ref "LD33") (pin "2") (pinfunction "ANODE_2") (pintype "power_in"))
      (node (ref "R49") (pin "2") (pinfunction "2_2") (pintype "passive"))
      (node (ref "R52") (pin "2") (pinfunction "2_2") (pintype "passive"))
      (node (ref "R53") (pin "2") (pinfunction "2_2") (pintype "passive"))
      (node (ref "R57") (pin "2") (pinfunction "2_2") (pintype "passive"))
      (node (ref "R61") (pin "2") (pinfunction "2_2") (pintype "passive"))
      (node (ref "R62") (pin "2") (pinfunction "2_2") (pintype "passive"))
      (node (ref "U1") (pin "1") (pinfunction "VDD_2_1") (pintype "power_in"))
      (node (ref "U1") (pin "22") (pinfunction "VDD_22") (pintype "power_in"))
      (node (ref "U1") (pin "5") (pinfunction "VOUT33_5") (pintype "output"))
      (node (ref "U1") (pin "9") (pinfunction "VDDA_9") (pintype "power_in"))
      (node (ref "U19") (pin "1") (pinfunction "VCC_1") (pintype "power_in"))
      (node (ref "U2") (pin "1") (pinfunction "VDD_1") (pintype "power_in"))
      (node (ref "U2") (pin "4") (pinfunction "VDDIO_4") (pintype "power_in"))
      (node (ref "U3") (pin "1") (pinfunction "VDDIO_1") (pintype "power_in"))
      (node (ref "U3") (pin "14") (pinfunction "VDD_14") (pintype "power_in"))
      (node (ref "U5") (pin "26") (pinfunction "VCC_26") (pintype "power_in"))
      (node (ref "X1") (pin "P$1") (pinfunction "1_P$1") (pintype "passive"))
      (node (ref "X2") (pin "P$1") (pinfunction "1_P$1") (pintype "passive"))
      (node (ref "X7") (pin "3") (pinfunction "3_3") (pintype "passive"))
    )
    (net (code "2") (name "+5V") (class "Default")
      (node (ref "C14") (pin "2") (pinfunction "2_2") (pintype "passive"))
      (node (ref "C2") (pin "2") (pinfunction "2_2") (pintype "passive"))
      (node (ref "D4") (pin "1") (pinfunction "A1_1") (pintype "passive"))
      (node (ref "R50") (pin "2") (pinfunction "2_2") (pintype "passive"))
      (node (ref "R59") (pin "2") (pinfunction "2_2") (pintype "passive"))
      (node (ref "U4") (pin "4") (pinfunction "VDD_4") (pintype "power_in"))
    )
    (net (code "3") (name "ACC-INT") (class "Default")
      (node (ref "U1") (pin "18") (pinfunction "PTA1_18") (pintype "bidirectional"))
      (node (ref "U3") (pin "11") (pinfunction "INT1_11") (pintype "output"))
    )
    (net (code "4") (name "BL-LINK") (class "Default")
      (node (ref "U1") (pin "33") (pinfunction "PTC0_33") (pintype "bidirectional"))
      (node (ref "U5") (pin "38") (pinfunction "SPI_CLK/SIO_25_38") (pintype "bidirectional"))
    )
    (net (code "5") (name "BL-RESET") (class "Default")
      (node (ref "U1") (pin "34") (pinfunction "PTC1/LLWU_P6_34") (pintype "bidirectional"))
      (node (ref "U5") (pin "7") (pinfunction "RESET/SIO_21_7") (pintype "bidirectional"))
      (node (ref "X2") (pin "P$10") (pinfunction "10_P$10") (pintype "passive"))
    )
    (net (code "6") (name "BL-SWD-CLK") (class "Default")
      (node (ref "U5") (pin "6") (pinfunction "SWDCLK_6") (pintype "bidirectional"))
      (node (ref "X2") (pin "P$4") (pinfunction "4_P$4") (pintype "passive"))
    )
    (net (code "7") (name "BL-SWD-IO") (class "Default")
      (node (ref "U5") (pin "5") (pinfunction "SWDIO_5") (pintype "bidirectional"))
      (node (ref "X2") (pin "P$2") (pinfunction "2_P$2") (pintype "passive"))
    )
    (net (code "8") (name "CHR-STAT") (class "Default")
      (node (ref "R52") (pin "1") (pinfunction "1_1") (pintype "passive"))
      (node (ref "U1") (pin "45") (pinfunction "PTD4/LLWU_P14_45") (pintype "bidirectional"))
      (node (ref "U4") (pin "1") (pinfunction "STAT_1") (pintype "output"))
    )
    (net (code "9") (name "D1-B") (class "Default")
      (node (ref "R66") (pin "1") (pinfunction "1_1") (pintype "passive"))
      (node (ref "U6") (pin "2") (pinfunction "QC_2") (pintype "output"))
    )
    (net (code "10") (name "D1-G") (class "Default")
      (node (ref "R65") (pin "1") (pinfunction "1_1") (pintype "passive"))
      (node (ref "U6") (pin "1") (pinfunction "QB_1") (pintype "output"))
    )
    (net (code "11") (name "D1-R") (class "Default")
      (node (ref "R64") (pin "1") (pinfunction "1_1") (pintype "passive"))
      (node (ref "U6") (pin "15") (pinfunction "QA_15") (pintype "output"))
    )
    (net (code "12") (name "D2-B") (class "Default")
      (node (ref "R69") (pin "1") (pinfunction "1_1") (pintype "passive"))
      (node (ref "U6") (pin "5") (pinfunction "QF_5") (pintype "output"))
    )
    (net (code "13") (name "D2-G") (class "Default")
      (node (ref "R68") (pin "1") (pinfunction "1_1") (pintype "passive"))
      (node (ref "U6") (pin "4") (pinfunction "QE_4") (pintype "output"))
    )
    (net (code "14") (name "D2-R") (class "Default")
      (node (ref "R67") (pin "1") (pinfunction "1_1") (pintype "passive"))
      (node (ref "U6") (pin "3") (pinfunction "QD_3") (pintype "output"))
    )
    (net (code "15") (name "D3-B") (class "Default")
      (node (ref "R72") (pin "1") (pinfunction "1_1") (pintype "passive"))
      (node (ref "U7") (pin "15") (pinfunction "QA_15") (pintype "output"))
    )
    (net (code "16") (name "D3-G") (class "Default")
      (node (ref "R71") (pin "1") (pinfunction "1_1") (pintype "passive"))
      (node (ref "U6") (pin "7") (pinfunction "QH_7") (pintype "output"))
    )
    (net (code "17") (name "D3-R") (class "Default")
      (node (ref "R70") (pin "1") (pinfunction "1_1") (pintype "passive"))
      (node (ref "U6") (pin "6") (pinfunction "QG_6") (pintype "output"))
    )
    (net (code "18") (name "D4-B") (class "Default")
      (node (ref "R75") (pin "1") (pinfunction "1_1") (pintype "passive"))
      (node (ref "U7") (pin "3") (pinfunction "QD_3") (pintype "output"))
    )
    (net (code "19") (name "D4-G") (class "Default")
      (node (ref "R74") (pin "1") (pinfunction "1_1") (pintype "passive"))
      (node (ref "U7") (pin "2") (pinfunction "QC_2") (pintype "output"))
    )
    (net (code "20") (name "D4-R") (class "Default")
      (node (ref "R73") (pin "1") (pinfunction "1_1") (pintype "passive"))
      (node (ref "U7") (pin "1") (pinfunction "QB_1") (pintype "output"))
    )
    (net (code "21") (name "D5-B") (class "Default")
      (node (ref "R78") (pin "1") (pinfunction "1_1") (pintype "passive"))
      (node (ref "U7") (pin "6") (pinfunction "QG_6") (pintype "output"))
    )
    (net (code "22") (name "D5-G") (class "Default")
      (node (ref "R77") (pin "1") (pinfunction "1_1") (pintype "passive"))
      (node (ref "U7") (pin "5") (pinfunction "QF_5") (pintype "output"))
    )
    (net (code "23") (name "D5-R") (class "Default")
      (node (ref "R76") (pin "1") (pinfunction "1_1") (pintype "passive"))
      (node (ref "U7") (pin "4") (pinfunction "QE_4") (pintype "output"))
    )
    (net (code "24") (name "D6-B") (class "Default")
      (node (ref "R81") (pin "1") (pinfunction "1_1") (pintype "passive"))
      (node (ref "U8") (pin "1") (pinfunction "QB_1") (pintype "output"))
    )
    (net (code "25") (name "D6-G") (class "Default")
      (node (ref "R80") (pin "1") (pinfunction "1_1") (pintype "passive"))
      (node (ref "U8") (pin "15") (pinfunction "QA_15") (pintype "output"))
    )
    (net (code "26") (name "D6-R") (class "Default")
      (node (ref "R79") (pin "1") (pinfunction "1_1") (pintype "passive"))
      (node (ref "U7") (pin "7") (pinfunction "QH_7") (pintype "output"))
    )
    (net (code "27") (name "D7-B") (class "Default")
      (node (ref "R84") (pin "1") (pinfunction "1_1") (pintype "passive"))
      (node (ref "U8") (pin "4") (pinfunction "QE_4") (pintype "output"))
    )
    (net (code "28") (name "D7-G") (class "Default")
      (node (ref "R83") (pin "1") (pinfunction "1_1") (pintype "passive"))
      (node (ref "U8") (pin "3") (pinfunction "QD_3") (pintype "output"))
    )
    (net (code "29") (name "D7-R") (class "Default")
      (node (ref "R82") (pin "1") (pinfunction "1_1") (pintype "passive"))
      (node (ref "U8") (pin "2") (pinfunction "QC_2") (pintype "output"))
    )
    (net (code "30") (name "D8-B") (class "Default")
      (node (ref "R87") (pin "1") (pinfunction "1_1") (pintype "passive"))
      (node (ref "U8") (pin "7") (pinfunction "QH_7") (pintype "output"))
    )
    (net (code "31") (name "D8-G") (class "Default")
      (node (ref "R86") (pin "1") (pinfunction "1_1") (pintype "passive"))
      (node (ref "U8") (pin "6") (pinfunction "QG_6") (pintype "output"))
    )
    (net (code "32") (name "D8-R") (class "Default")
      (node (ref "R85") (pin "1") (pinfunction "1_1") (pintype "passive"))
      (node (ref "U8") (pin "5") (pinfunction "QF_5") (pintype "output"))
    )
    (net (code "33") (name "D9-B") (class "Default")
      (node (ref "R90") (pin "1") (pinfunction "1_1") (pintype "passive"))
      (node (ref "U9") (pin "2") (pinfunction "QC_2") (pintype "output"))
    )
    (net (code "34") (name "D9-G") (class "Default")
      (node (ref "R89") (pin "1") (pinfunction "1_1") (pintype "passive"))
      (node (ref "U9") (pin "1") (pinfunction "QB_1") (pintype "output"))
    )
    (net (code "35") (name "D9-R") (class "Default")
      (node (ref "R88") (pin "1") (pinfunction "1_1") (pintype "passive"))
      (node (ref "U9") (pin "15") (pinfunction "QA_15") (pintype "output"))
    )
    (net (code "36") (name "D10-B") (class "Default")
      (node (ref "R93") (pin "1") (pinfunction "1_1") (pintype "passive"))
      (node (ref "U9") (pin "5") (pinfunction "QF_5") (pintype "output"))
    )
    (net (code "37") (name "D10-G") (class "Default")
      (node (ref "R92") (pin "1") (pinfunction "1_1") (pintype "passive"))
      (node (ref "U9") (pin "4") (pinfunction "QE_4") (pintype "output"))
    )
    (net (code "38") (name "D10-R") (class "Default")
      (node (ref "R91") (pin "1") (pinfunction "1_1") (pintype "passive"))
      (node (ref "U9") (pin "3") (pinfunction "QD_3") (pintype "output"))
    )
    (net (code "39") (name "D11-B") (class "Default")
      (node (ref "R96") (pin "1") (pinfunction "1_1") (pintype "passive"))
      (node (ref "U10") (pin "15") (pinfunction "QA_15") (pintype "output"))
    )
    (net (code "40") (name "D11-G") (class "Default")
      (node (ref "R95") (pin "1") (pinfunction "1_1") (pintype "passive"))
      (node (ref "U9") (pin "7") (pinfunction "QH_7") (pintype "output"))
    )
    (net (code "41") (name "D11-R") (class "Default")
      (node (ref "R94") (pin "1") (pinfunction "1_1") (pintype "passive"))
      (node (ref "U9") (pin "6") (pinfunction "QG_6") (pintype "output"))
    )
    (net (code "42") (name "D12-B") (class "Default")
      (node (ref "R99") (pin "1") (pinfunction "1_1") (pintype "passive"))
      (node (ref "U10") (pin "3") (pinfunction "QD_3") (pintype "output"))
    )
    (net (code "43") (name "D12-G") (class "Default")
      (node (ref "R98") (pin "1") (pinfunction "1_1") (pintype "passive"))
      (node (ref "U10") (pin "2") (pinfunction "QC_2") (pintype "output"))
    )
    (net (code "44") (name "D12-R") (class "Default")
      (node (ref "R97") (pin "1") (pinfunction "1_1") (pintype "passive"))
      (node (ref "U10") (pin "1") (pinfunction "QB_1") (pintype "output"))
    )
    (net (code "45") (name "D13-B") (class "Default")
      (node (ref "R102") (pin "1") (pinfunction "1_1") (pintype "passive"))
      (node (ref "U10") (pin "6") (pinfunction "QG_6") (pintype "output"))
    )
    (net (code "46") (name "D13-G") (class "Default")
      (node (ref "R101") (pin "1") (pinfunction "1_1") (pintype "passive"))
      (node (ref "U10") (pin "5") (pinfunction "QF_5") (pintype "output"))
    )
    (net (code "47") (name "D13-R") (class "Default")
      (node (ref "R100") (pin "1") (pinfunction "1_1") (pintype "passive"))
      (node (ref "U10") (pin "4") (pinfunction "QE_4") (pintype "output"))
    )
    (net (code "48") (name "D14-B") (class "Default")
      (node (ref "R105") (pin "1") (pinfunction "1_1") (pintype "passive"))
      (node (ref "U11") (pin "1") (pinfunction "QB_1") (pintype "output"))
    )
    (net (code "49") (name "D14-G") (class "Default")
      (node (ref "R104") (pin "1") (pinfunction "1_1") (pintype "passive"))
      (node (ref "U11") (pin "15") (pinfunction "QA_15") (pintype "output"))
    )
    (net (code "50") (name "D14-R") (class "Default")
      (node (ref "R103") (pin "1") (pinfunction "1_1") (pintype "passive"))
      (node (ref "U10") (pin "7") (pinfunction "QH_7") (pintype "output"))
    )
    (net (code "51") (name "D15-B") (class "Default")
      (node (ref "R108") (pin "1") (pinfunction "1_1") (pintype "passive"))
      (node (ref "U11") (pin "4") (pinfunction "QE_4") (pintype "output"))
    )
    (net (code "52") (name "D15-G") (class "Default")
      (node (ref "R107") (pin "1") (pinfunction "1_1") (pintype "passive"))
      (node (ref "U11") (pin "3") (pinfunction "QD_3") (pintype "output"))
    )
    (net (code "53") (name "D15-R") (class "Default")
      (node (ref "R106") (pin "1") (pinfunction "1_1") (pintype "passive"))
      (node (ref "U11") (pin "2") (pinfunction "QC_2") (pintype "output"))
    )
    (net (code "54") (name "D16-B") (class "Default")
      (node (ref "R111") (pin "1") (pinfunction "1_1") (pintype "passive"))
      (node (ref "U11") (pin "7") (pinfunction "QH_7") (pintype "output"))
    )
    (net (code "55") (name "D16-G") (class "Default")
      (node (ref "R110") (pin "1") (pinfunction "1_1") (pintype "passive"))
      (node (ref "U11") (pin "6") (pinfunction "QG_6") (pintype "output"))
    )
    (net (code "56") (name "D16-R") (class "Default")
      (node (ref "R109") (pin "1") (pinfunction "1_1") (pintype "passive"))
      (node (ref "U11") (pin "5") (pinfunction "QF_5") (pintype "output"))
    )
    (net (code "57") (name "D17-B") (class "Default")
      (node (ref "R4") (pin "1") (pinfunction "1_1") (pintype "passive"))
      (node (ref "U12") (pin "2") (pinfunction "QC_2") (pintype "output"))
    )
    (net (code "58") (name "D17-G") (class "Default")
      (node (ref "R3") (pin "1") (pinfunction "1_1") (pintype "passive"))
      (node (ref "U12") (pin "1") (pinfunction "QB_1") (pintype "output"))
    )
    (net (code "59") (name "D17-R") (class "Default")
      (node (ref "R2") (pin "1") (pinfunction "1_1") (pintype "passive"))
      (node (ref "U12") (pin "15") (pinfunction "QA_15") (pintype "output"))
    )
    (net (code "60") (name "D18-B") (class "Default")
      (node (ref "R7") (pin "1") (pinfunction "1_1") (pintype "passive"))
      (node (ref "U12") (pin "5") (pinfunction "QF_5") (pintype "output"))
    )
    (net (code "61") (name "D18-G") (class "Default")
      (node (ref "R6") (pin "1") (pinfunction "1_1") (pintype "passive"))
      (node (ref "U12") (pin "4") (pinfunction "QE_4") (pintype "output"))
    )
    (net (code "62") (name "D18-R") (class "Default")
      (node (ref "R5") (pin "1") (pinfunction "1_1") (pintype "passive"))
      (node (ref "U12") (pin "3") (pinfunction "QD_3") (pintype "output"))
    )
    (net (code "63") (name "D19-B") (class "Default")
      (node (ref "R10") (pin "1") (pinfunction "1_1") (pintype "passive"))
      (node (ref "U13") (pin "15") (pinfunction "QA_15") (pintype "output"))
    )
    (net (code "64") (name "D19-G") (class "Default")
      (node (ref "R9") (pin "1") (pinfunction "1_1") (pintype "passive"))
      (node (ref "U12") (pin "7") (pinfunction "QH_7") (pintype "output"))
    )
    (net (code "65") (name "D19-R") (class "Default")
      (node (ref "R8") (pin "1") (pinfunction "1_1") (pintype "passive"))
      (node (ref "U12") (pin "6") (pinfunction "QG_6") (pintype "output"))
    )
    (net (code "66") (name "D20-B") (class "Default")
      (node (ref "R13") (pin "1") (pinfunction "1_1") (pintype "passive"))
      (node (ref "U13") (pin "3") (pinfunction "QD_3") (pintype "output"))
    )
    (net (code "67") (name "D20-G") (class "Default")
      (node (ref "R12") (pin "1") (pinfunction "1_1") (pintype "passive"))
      (node (ref "U13") (pin "2") (pinfunction "QC_2") (pintype "output"))
    )
    (net (code "68") (name "D20-R") (class "Default")
      (node (ref "R11") (pin "1") (pinfunction "1_1") (pintype "passive"))
      (node (ref "U13") (pin "1") (pinfunction "QB_1") (pintype "output"))
    )
    (net (code "69") (name "D21-B") (class "Default")
      (node (ref "R16") (pin "1") (pinfunction "1_1") (pintype "passive"))
      (node (ref "U13") (pin "6") (pinfunction "QG_6") (pintype "output"))
    )
    (net (code "70") (name "D21-G") (class "Default")
      (node (ref "R15") (pin "1") (pinfunction "1_1") (pintype "passive"))
      (node (ref "U13") (pin "5") (pinfunction "QF_5") (pintype "output"))
    )
    (net (code "71") (name "D21-R") (class "Default")
      (node (ref "R14") (pin "1") (pinfunction "1_1") (pintype "passive"))
      (node (ref "U13") (pin "4") (pinfunction "QE_4") (pintype "output"))
    )
    (net (code "72") (name "D22-B") (class "Default")
      (node (ref "R19") (pin "1") (pinfunction "1_1") (pintype "passive"))
      (node (ref "U14") (pin "1") (pinfunction "QB_1") (pintype "output"))
    )
    (net (code "73") (name "D22-G") (class "Default")
      (node (ref "R18") (pin "1") (pinfunction "1_1") (pintype "passive"))
      (node (ref "U14") (pin "15") (pinfunction "QA_15") (pintype "output"))
    )
    (net (code "74") (name "D22-R") (class "Default")
      (node (ref "R17") (pin "1") (pinfunction "1_1") (pintype "passive"))
      (node (ref "U13") (pin "7") (pinfunction "QH_7") (pintype "output"))
    )
    (net (code "75") (name "D23-B") (class "Default")
      (node (ref "R22") (pin "1") (pinfunction "1_1") (pintype "passive"))
      (node (ref "U14") (pin "4") (pinfunction "QE_4") (pintype "output"))
    )
    (net (code "76") (name "D23-G") (class "Default")
      (node (ref "R21") (pin "1") (pinfunction "1_1") (pintype "passive"))
      (node (ref "U14") (pin "3") (pinfunction "QD_3") (pintype "output"))
    )
    (net (code "77") (name "D23-R") (class "Default")
      (node (ref "R20") (pin "1") (pinfunction "1_1") (pintype "passive"))
      (node (ref "U14") (pin "2") (pinfunction "QC_2") (pintype "output"))
    )
    (net (code "78") (name "D24-B") (class "Default")
      (node (ref "R25") (pin "1") (pinfunction "1_1") (pintype "passive"))
      (node (ref "U14") (pin "7") (pinfunction "QH_7") (pintype "output"))
    )
    (net (code "79") (name "D24-G") (class "Default")
      (node (ref "R24") (pin "1") (pinfunction "1_1") (pintype "passive"))
      (node (ref "U14") (pin "6") (pinfunction "QG_6") (pintype "output"))
    )
    (net (code "80") (name "D24-R") (class "Default")
      (node (ref "R23") (pin "1") (pinfunction "1_1") (pintype "passive"))
      (node (ref "U14") (pin "5") (pinfunction "QF_5") (pintype "output"))
    )
    (net (code "81") (name "D25-B") (class "Default")
      (node (ref "R28") (pin "1") (pinfunction "1_1") (pintype "passive"))
      (node (ref "U15") (pin "2") (pinfunction "QC_2") (pintype "output"))
    )
    (net (code "82") (name "D25-G") (class "Default")
      (node (ref "R27") (pin "1") (pinfunction "1_1") (pintype "passive"))
      (node (ref "U15") (pin "1") (pinfunction "QB_1") (pintype "output"))
    )
    (net (code "83") (name "D25-R") (class "Default")
      (node (ref "R26") (pin "1") (pinfunction "1_1") (pintype "passive"))
      (node (ref "U15") (pin "15") (pinfunction "QA_15") (pintype "output"))
    )
    (net (code "84") (name "D26-B") (class "Default")
      (node (ref "R31") (pin "1") (pinfunction "1_1") (pintype "passive"))
      (node (ref "U15") (pin "5") (pinfunction "QF_5") (pintype "output"))
    )
    (net (code "85") (name "D26-G") (class "Default")
      (node (ref "R30") (pin "1") (pinfunction "1_1") (pintype "passive"))
      (node (ref "U15") (pin "4") (pinfunction "QE_4") (pintype "output"))
    )
    (net (code "86") (name "D26-R") (class "Default")
      (node (ref "R29") (pin "1") (pinfunction "1_1") (pintype "passive"))
      (node (ref "U15") (pin "3") (pinfunction "QD_3") (pintype "output"))
    )
    (net (code "87") (name "D27-B") (class "Default")
      (node (ref "R34") (pin "1") (pinfunction "1_1") (pintype "passive"))
      (node (ref "U16") (pin "15") (pinfunction "QA_15") (pintype "output"))
    )
    (net (code "88") (name "D27-G") (class "Default")
      (node (ref "R33") (pin "1") (pinfunction "1_1") (pintype "passive"))
      (node (ref "U15") (pin "7") (pinfunction "QH_7") (pintype "output"))
    )
    (net (code "89") (name "D27-R") (class "Default")
      (node (ref "R32") (pin "1") (pinfunction "1_1") (pintype "passive"))
      (node (ref "U15") (pin "6") (pinfunction "QG_6") (pintype "output"))
    )
    (net (code "90") (name "D28-B") (class "Default")
      (node (ref "R37") (pin "1") (pinfunction "1_1") (pintype "passive"))
      (node (ref "U16") (pin "3") (pinfunction "QD_3") (pintype "output"))
    )
    (net (code "91") (name "D28-G") (class "Default")
      (node (ref "R36") (pin "1") (pinfunction "1_1") (pintype "passive"))
      (node (ref "U16") (pin "2") (pinfunction "QC_2") (pintype "output"))
    )
    (net (code "92") (name "D28-R") (class "Default")
      (node (ref "R35") (pin "1") (pinfunction "1_1") (pintype "passive"))
      (node (ref "U16") (pin "1") (pinfunction "QB_1") (pintype "output"))
    )
    (net (code "93") (name "D29-B") (class "Default")
      (node (ref "R40") (pin "1") (pinfunction "1_1") (pintype "passive"))
      (node (ref "U16") (pin "6") (pinfunction "QG_6") (pintype "output"))
    )
    (net (code "94") (name "D29-G") (class "Default")
      (node (ref "R39") (pin "1") (pinfunction "1_1") (pintype "passive"))
      (node (ref "U16") (pin "5") (pinfunction "QF_5") (pintype "output"))
    )
    (net (code "95") (name "D29-R") (class "Default")
      (node (ref "R38") (pin "1") (pinfunction "1_1") (pintype "passive"))
      (node (ref "U16") (pin "4") (pinfunction "QE_4") (pintype "output"))
    )
    (net (code "96") (name "D30-B") (class "Default")
      (node (ref "R43") (pin "1") (pinfunction "1_1") (pintype "passive"))
      (node (ref "U17") (pin "1") (pinfunction "QB_1") (pintype "output"))
    )
    (net (code "97") (name "D30-G") (class "Default")
      (node (ref "R42") (pin "1") (pinfunction "1_1") (pintype "passive"))
      (node (ref "U17") (pin "15") (pinfunction "QA_15") (pintype "output"))
    )
    (net (code "98") (name "D30-R") (class "Default")
      (node (ref "R41") (pin "1") (pinfunction "1_1") (pintype "passive"))
      (node (ref "U16") (pin "7") (pinfunction "QH_7") (pintype "output"))
    )
    (net (code "99") (name "D31-B") (class "Default")
      (node (ref "R46") (pin "1") (pinfunction "1_1") (pintype "passive"))
      (node (ref "U17") (pin "4") (pinfunction "QE_4") (pintype "output"))
    )
    (net (code "100") (name "D31-G") (class "Default")
      (node (ref "R45") (pin "1") (pinfunction "1_1") (pintype "passive"))
      (node (ref "U17") (pin "3") (pinfunction "QD_3") (pintype "output"))
    )
    (net (code "101") (name "D31-R") (class "Default")
      (node (ref "R44") (pin "1") (pinfunction "1_1") (pintype "passive"))
      (node (ref "U17") (pin "2") (pinfunction "QC_2") (pintype "output"))
    )
    (net (code "102") (name "D32-B") (class "Default")
      (node (ref "R56") (pin "1") (pinfunction "1_1") (pintype "passive"))
      (node (ref "U17") (pin "7") (pinfunction "QH_7") (pintype "output"))
    )
    (net (code "103") (name "D32-G") (class "Default")
      (node (ref "R48") (pin "1") (pinfunction "1_1") (pintype "passive"))
      (node (ref "U17") (pin "6") (pinfunction "QG_6") (pintype "output"))
    )
    (net (code "104") (name "D32-R") (class "Default")
      (node (ref "R47") (pin "1") (pinfunction "1_1") (pintype "passive"))
      (node (ref "U17") (pin "5") (pinfunction "QF_5") (pintype "output"))
    )
    (net (code "105") (name "GND") (class "Default")
      (node (ref "C1") (pin "2") (pinfunction "2_2") (pintype "passive"))
      (node (ref "C10") (pin "1") (pinfunction "1_1") (pintype "passive"))
      (node (ref "C11") (pin "2") (pinfunction "2_2") (pintype "passive"))
      (node (ref "C12") (pin "1") (pinfunction "1_1") (pintype "passive"))
      (node (ref "C13") (pin "1") (pinfunction "1_1") (pintype "passive"))
      (node (ref "C14") (pin "1") (pinfunction "1_1") (pintype "passive"))
      (node (ref "C15") (pin "2") (pinfunction "2_2") (pintype "passive"))
      (node (ref "C16") (pin "1") (pinfunction "1_1") (pintype "passive"))
      (node (ref "C17") (pin "1") (pinfunction "1_1") (pintype "passive"))
      (node (ref "C18") (pin "2") (pinfunction "2_2") (pintype "passive"))
      (node (ref "C19") (pin "2") (pinfunction "2_2") (pintype "passive"))
      (node (ref "C2") (pin "1") (pinfunction "1_1") (pintype "passive"))
      (node (ref "C21") (pin "2") (pinfunction "2_2") (pintype "passive"))
      (node (ref "C22") (pin "2") (pinfunction "2_2") (pintype "passive"))
      (node (ref "C23") (pin "2") (pinfunction "2_2") (pintype "passive"))
      (node (ref "C24") (pin "2") (pinfunction "2_2") (pintype "passive"))
      (node (ref "C25") (pin "2") (pinfunction "2_2") (pintype "passive"))
      (node (ref "C26") (pin "2") (pinfunction "2_2") (pintype "passive"))
      (node (ref "C27") (pin "2") (pinfunction "2_2") (pintype "passive"))
      (node (ref "C28") (pin "2") (pinfunction "2_2") (pintype "passive"))
      (node (ref "C29") (pin "2") (pinfunction "2_2") (pintype "passive"))
      (node (ref "C3") (pin "2") (pinfunction "2_2") (pintype "passive"))
      (node (ref "C30") (pin "2") (pinfunction "2_2") (pintype "passive"))
      (node (ref "C4") (pin "2") (pinfunction "2_2") (pintype "passive"))
      (node (ref "C5") (pin "2") (pinfunction "2_2") (pintype "passive"))
      (node (ref "C6") (pin "2") (pinfunction "2_2") (pintype "passive"))
      (node (ref "C7") (pin "2") (pinfunction "2_2") (pintype "passive"))
      (node (ref "C8") (pin "2") (pinfunction "2_2") (pintype "passive"))
      (node (ref "C9") (pin "1") (pinfunction "1_1") (pintype "passive"))
      (node (ref "D1") (pin "3") (pinfunction "A_3") (pintype "passive"))
      (node (ref "D2") (pin "3") (pinfunction "A_3") (pintype "passive"))
      (node (ref "Q2") (pin "2") (pinfunction "2_2") (pintype "passive"))
      (node (ref "Q2") (pin "4") (pinfunction "4_4") (pintype "passive"))
      (node (ref "R51") (pin "1") (pinfunction "1_1") (pintype "passive"))
      (node (ref "R60") (pin "2") (pinfunction "2_2") (pintype "passive"))
      (node (ref "R63") (pin "1") (pinfunction "1_1") (pintype "passive"))
      (node (ref "S1") (pin "1") (pinfunction "P_1") (pintype "passive"))
      (node (ref "S1") (pin "2") (pinfunction "P1_2") (pintype "passive"))
      (node (ref "U1") (pin "11") (pinfunction "VREFL_11") (pintype "passive"))
      (node (ref "U1") (pin "12") (pinfunction "VSSA_12") (pintype "power_in"))
      (node (ref "U1") (pin "2") (pinfunction "VSS_2_2") (pintype "power_in"))
      (node (ref "U1") (pin "23") (pinfunction "VSS_23") (pintype "power_in"))
      (node (ref "U10") (pin "8") (pinfunction "GND_8") (pintype "passive"))
      (node (ref "U11") (pin "8") (pinfunction "GND_8") (pintype "passive"))
      (node (ref "U12") (pin "8") (pinfunction "GND_8") (pintype "passive"))
      (node (ref "U13") (pin "8") (pinfunction "GND_8") (pintype "passive"))
      (node (ref "U14") (pin "8") (pinfunction "GND_8") (pintype "passive"))
      (node (ref "U15") (pin "8") (pinfunction "GND_8") (pintype "passive"))
      (node (ref "U16") (pin "8") (pinfunction "GND_8") (pintype "passive"))
      (node (ref "U17") (pin "8") (pinfunction "GND_8") (pintype "passive"))
      (node (ref "U18") (pin "3") (pinfunction "GND_3") (pintype "power_in"))
      (node (ref "U19") (pin "3") (pinfunction "GND_3") (pintype "power_in"))
      (node (ref "U2") (pin "3") (pinfunction "GND_3") (pintype "power_in"))
      (node (ref "U3") (pin "10") (pinfunction "GND_2_10") (pintype "passive"))
      (node (ref "U3") (pin "12") (pinfunction "GND_12") (pintype "passive"))
      (node (ref "U3") (pin "5") (pinfunction "GND_3_5") (pintype "passive"))
      (node (ref "U3") (pin "7") (pinfunction "SA0_7") (pintype "input"))
      (node (ref "U4") (pin "2") (pinfunction "VSS_2") (pintype "power_in"))
      (node (ref "U5") (pin "1") (pinfunction "GND_1") (pintype "power_in"))
      (node (ref "U5") (pin "16") (pinfunction "GND_16") (pintype "power_in"))
      (node (ref "U5") (pin "27") (pinfunction "GND_27") (pintype "power_in"))
      (node (ref "U5") (pin "28") (pinfunction "SIO_13/AUTORUN_28") (pintype "bidirectional"))
      (node (ref "U5") (pin "39") (pinfunction "GND_39") (pintype "power_in"))
      (node (ref "U6") (pin "8") (pinfunction "GND_8") (pintype "passive"))
      (node (ref "U7") (pin "8") (pinfunction "GND_8") (pintype "passive"))
      (node (ref "U8") (pin "8") (pinfunction "GND_8") (pintype "passive"))
      (node (ref "U9") (pin "8") (pinfunction "GND_8") (pintype "passive"))
      (node (ref "X1") (pin "P$3") (pinfunction "3_P$3") (pintype "passive"))
      (node (ref "X1") (pin "P$5") (pinfunction "5_P$5") (pintype "passive"))
      (node (ref "X2") (pin "P$3") (pinfunction "3_P$3") (pintype "passive"))
      (node (ref "X2") (pin "P$5") (pinfunction "5_P$5") (pintype "passive"))
      (node (ref "X3") (pin "1") (pinfunction "1_1") (pintype "passive"))
      (node (ref "X4") (pin "5") (pinfunction "5_5") (pintype "input"))
      (node (ref "X5") (pin "8") (pinfunction "8_8") (pintype "passive"))
      (node (ref "X6") (pin "8") (pinfunction "8_8") (pintype "passive"))
      (node (ref "X7") (pin "4") (pinfunction "4_4") (pintype "passive"))
    )
    (net (code "106") (name "HALL-SENSOR") (class "Default")
      (node (ref "R53") (pin "1") (pinfunction "1_1") (pintype "passive"))
      (node (ref "U1") (pin "43") (pinfunction "PTD2/LLWU_P13_43") (pintype "bidirectional"))
      (node (ref "U18") (pin "2") (pinfunction "OUT_2") (pintype "output"))
      (node (ref "U19") (pin "2") (pinfunction "OUT_2") (pintype "output"))
    )
    (net (code "107") (name "HALL-VCC") (class "Default")
      (node (ref "C27") (pin "1") (pinfunction "1_1") (pintype "passive"))
      (node (ref "U1") (pin "47") (pinfunction "PTD6/LLWU_P15_47") (pintype "bidirectional"))
      (node (ref "U18") (pin "1") (pinfunction "VCC_1") (pintype "power_in"))
    )
    (net (code "108") (name "I2C-SCL") (class "Default")
      (node (ref "R62") (pin "1") (pinfunction "1_1") (pintype "passive"))
      (node (ref "U1") (pin "27") (pinfunction "PTB0/LLWU_P5_27") (pintype "bidirectional"))
      (node (ref "U2") (pin "8") (pinfunction "SCL_8") (pintype "input"))
      (node (ref "U3") (pin "4") (pinfunction "SCL_4") (pintype "input"))
      (node (ref "U5") (pin "36") (pinfunction "I2C_CLK/SIO_27_36") (pintype "bidirectional"))
      (node (ref "X7") (pin "2") (pinfunction "2_2") (pintype "passive"))
    )
    (net (code "109") (name "I2C-SDA") (class "Default")
      (node (ref "R61") (pin "1") (pinfunction "1_1") (pintype "passive"))
      (node (ref "U1") (pin "28") (pinfunction "PTB1_28") (pintype "bidirectional"))
      (node (ref "U2") (pin "7") (pinfunction "SDA_7") (pintype "bidirectional"))
      (node (ref "U3") (pin "6") (pinfunction "SDA_6") (pintype "input"))
      (node (ref "U5") (pin "37") (pinfunction "I2C_SDA/SIO_26_37") (pintype "bidirectional"))
      (node (ref "X7") (pin "1") (pinfunction "1_1") (pintype "passive"))
    )
    (net (code "110") (name "LED-B") (class "Default")
      (node (ref "R115") (pin "1") (pinfunction "1_1") (pintype "passive"))
      (node (ref "U1") (pin "48") (pinfunction "PTD7_48") (pintype "bidirectional"))
    )
    (net (code "111") (name "LED-G") (class "Default")
      (node (ref "R114") (pin "1") (pinfunction "1_1") (pintype "passive"))
      (node (ref "U1") (pin "44") (pinfunction "PTD3_44") (pintype "bidirectional"))
    )
    (net (code "112") (name "LED-R") (class "Default")
      (node (ref "R58") (pin "1") (pinfunction "1_1") (pintype "passive"))
      (node (ref "U1") (pin "40") (pinfunction "PTC7_40") (pintype "bidirectional"))
    )
    (net (code "113") (name "MODE") (class "Default")
      (node (ref "R49") (pin "1") (pinfunction "1_1") (pintype "passive"))
      (node (ref "S1") (pin "3") (pinfunction "S_3") (pintype "passive"))
      (node (ref "S1") (pin "4") (pinfunction "S1_4") (pintype "passive"))
      (node (ref "U1") (pin "41") (pinfunction "PTD0/LLWU_P12_41") (pintype "bidirectional"))
    )
    (net (code "114") (name "Net-(D1-K1)") (class "Default")
      (node (ref "D1") (pin "1") (pinfunction "K1_1") (pintype "passive"))
      (node (ref "R54") (pin "1") (pinfunction "1_1") (pintype "passive"))
      (node (ref "X4") (pin "2") (pinfunction "2_2") (pintype "input"))
    )
    (net (code "115") (name "Net-(D1-K2)") (class "Default")
      (node (ref "D1") (pin "2") (pinfunction "K2_2") (pintype "passive"))
      (node (ref "R55") (pin "1") (pinfunction "1_1") (pintype "passive"))
      (node (ref "X4") (pin "3") (pinfunction "3_3") (pintype "input"))
    )
    (net (code "116") (name "Net-(LD1-BLUE)") (class "Default")
      (node (ref "LD1") (pin "3") (pinfunction "BLUE_3") (pintype "bidirectional"))
      (node (ref "R66") (pin "2") (pinfunction "2_2") (pintype "passive"))
    )
    (net (code "117") (name "Net-(LD1-GRN)") (class "Default")
      (node (ref "LD1") (pin "4") (pinfunction "GRN_4") (pintype "bidirectional"))
      (node (ref "R65") (pin "2") (pinfunction "2_2") (pintype "passive"))
    )
    (net (code "118") (name "Net-(LD1-RED)") (class "Default")
      (node (ref "LD1") (pin "1") (pinfunction "RED_1") (pintype "bidirectional"))
      (node (ref "R64") (pin "2") (pinfunction "2_2") (pintype "passive"))
    )
    (net (code "119") (name "Net-(LD2-BLUE)") (class "Default")
      (node (ref "LD2") (pin "3") (pinfunction "BLUE_3") (pintype "bidirectional"))
      (node (ref "R69") (pin "2") (pinfunction "2_2") (pintype "passive"))
    )
    (net (code "120") (name "Net-(LD2-GRN)") (class "Default")
      (node (ref "LD2") (pin "4") (pinfunction "GRN_4") (pintype "bidirectional"))
      (node (ref "R68") (pin "2") (pinfunction "2_2") (pintype "passive"))
    )
    (net (code "121") (name "Net-(LD2-RED)") (class "Default")
      (node (ref "LD2") (pin "1") (pinfunction "RED_1") (pintype "bidirectional"))
      (node (ref "R67") (pin "2") (pinfunction "2_2") (pintype "passive"))
    )
    (net (code "122") (name "Net-(LD3-BLUE)") (class "Default")
      (node (ref "LD3") (pin "3") (pinfunction "BLUE_3") (pintype "bidirectional"))
      (node (ref "R72") (pin "2") (pinfunction "2_2") (pintype "passive"))
    )
    (net (code "123") (name "Net-(LD3-GRN)") (class "Default")
      (node (ref "LD3") (pin "4") (pinfunction "GRN_4") (pintype "bidirectional"))
      (node (ref "R71") (pin "2") (pinfunction "2_2") (pintype "passive"))
    )
    (net (code "124") (name "Net-(LD3-RED)") (class "Default")
      (node (ref "LD3") (pin "1") (pinfunction "RED_1") (pintype "bidirectional"))
      (node (ref "R70") (pin "2") (pinfunction "2_2") (pintype "passive"))
    )
    (net (code "125") (name "Net-(LD4-BLUE)") (class "Default")
      (node (ref "LD4") (pin "3") (pinfunction "BLUE_3") (pintype "bidirectional"))
      (node (ref "R75") (pin "2") (pinfunction "2_2") (pintype "passive"))
    )
    (net (code "126") (name "Net-(LD4-GRN)") (class "Default")
      (node (ref "LD4") (pin "4") (pinfunction "GRN_4") (pintype "bidirectional"))
      (node (ref "R74") (pin "2") (pinfunction "2_2") (pintype "passive"))
    )
    (net (code "127") (name "Net-(LD4-RED)") (class "Default")
      (node (ref "LD4") (pin "1") (pinfunction "RED_1") (pintype "bidirectional"))
      (node (ref "R73") (pin "2") (pinfunction "2_2") (pintype "passive"))
    )
    (net (code "128") (name "Net-(LD5-BLUE)") (class "Default")
      (node (ref "LD5") (pin "3") (pinfunction "BLUE_3") (pintype "bidirectional"))
      (node (ref "R78") (pin "2") (pinfunction "2_2") (pintype "passive"))
    )
    (net (code "129") (name "Net-(LD5-GRN)") (class "Default")
      (node (ref "LD5") (pin "4") (pinfunction "GRN_4") (pintype "bidirectional"))
      (node (ref "R77") (pin "2") (pinfunction "2_2") (pintype "passive"))
    )
    (net (code "130") (name "Net-(LD5-RED)") (class "Default")
      (node (ref "LD5") (pin "1") (pinfunction "RED_1") (pintype "bidirectional"))
      (node (ref "R76") (pin "2") (pinfunction "2_2") (pintype "passive"))
    )
    (net (code "131") (name "Net-(LD6-BLUE)") (class "Default")
      (node (ref "LD6") (pin "3") (pinfunction "BLUE_3") (pintype "bidirectional"))
      (node (ref "R81") (pin "2") (pinfunction "2_2") (pintype "passive"))
    )
    (net (code "132") (name "Net-(LD6-GRN)") (class "Default")
      (node (ref "LD6") (pin "4") (pinfunction "GRN_4") (pintype "bidirectional"))
      (node (ref "R80") (pin "2") (pinfunction "2_2") (pintype "passive"))
    )
    (net (code "133") (name "Net-(LD6-RED)") (class "Default")
      (node (ref "LD6") (pin "1") (pinfunction "RED_1") (pintype "bidirectional"))
      (node (ref "R79") (pin "2") (pinfunction "2_2") (pintype "passive"))
    )
    (net (code "134") (name "Net-(LD7-BLUE)") (class "Default")
      (node (ref "LD7") (pin "3") (pinfunction "BLUE_3") (pintype "bidirectional"))
      (node (ref "R84") (pin "2") (pinfunction "2_2") (pintype "passive"))
    )
    (net (code "135") (name "Net-(LD7-GRN)") (class "Default")
      (node (ref "LD7") (pin "4") (pinfunction "GRN_4") (pintype "bidirectional"))
      (node (ref "R83") (pin "2") (pinfunction "2_2") (pintype "passive"))
    )
    (net (code "136") (name "Net-(LD7-RED)") (class "Default")
      (node (ref "LD7") (pin "1") (pinfunction "RED_1") (pintype "bidirectional"))
      (node (ref "R82") (pin "2") (pinfunction "2_2") (pintype "passive"))
    )
    (net (code "137") (name "Net-(LD8-BLUE)") (class "Default")
      (node (ref "LD8") (pin "3") (pinfunction "BLUE_3") (pintype "bidirectional"))
      (node (ref "R87") (pin "2") (pinfunction "2_2") (pintype "passive"))
    )
    (net (code "138") (name "Net-(LD8-GRN)") (class "Default")
      (node (ref "LD8") (pin "4") (pinfunction "GRN_4") (pintype "bidirectional"))
      (node (ref "R86") (pin "2") (pinfunction "2_2") (pintype "passive"))
    )
    (net (code "139") (name "Net-(LD8-RED)") (class "Default")
      (node (ref "LD8") (pin "1") (pinfunction "RED_1") (pintype "bidirectional"))
      (node (ref "R85") (pin "2") (pinfunction "2_2") (pintype "passive"))
    )
    (net (code "140") (name "Net-(LD9-BLUE)") (class "Default")
      (node (ref "LD9") (pin "3") (pinfunction "BLUE_3") (pintype "bidirectional"))
      (node (ref "R90") (pin "2") (pinfunction "2_2") (pintype "passive"))
    )
    (net (code "141") (name "Net-(LD9-GRN)") (class "Default")
      (node (ref "LD9") (pin "4") (pinfunction "GRN_4") (pintype "bidirectional"))
      (node (ref "R89") (pin "2") (pinfunction "2_2") (pintype "passive"))
    )
    (net (code "142") (name "Net-(LD9-RED)") (class "Default")
      (node (ref "LD9") (pin "1") (pinfunction "RED_1") (pintype "bidirectional"))
      (node (ref "R88") (pin "2") (pinfunction "2_2") (pintype "passive"))
    )
    (net (code "143") (name "Net-(LD10-BLUE)") (class "Default")
      (node (ref "LD10") (pin "3") (pinfunction "BLUE_3") (pintype "bidirectional"))
      (node (ref "R93") (pin "2") (pinfunction "2_2") (pintype "passive"))
    )
    (net (code "144") (name "Net-(LD10-GRN)") (class "Default")
      (node (ref "LD10") (pin "4") (pinfunction "GRN_4") (pintype "bidirectional"))
      (node (ref "R92") (pin "2") (pinfunction "2_2") (pintype "passive"))
    )
    (net (code "145") (name "Net-(LD10-RED)") (class "Default")
      (node (ref "LD10") (pin "1") (pinfunction "RED_1") (pintype "bidirectional"))
      (node (ref "R91") (pin "2") (pinfunction "2_2") (pintype "passive"))
    )
    (net (code "146") (name "Net-(LD11-BLUE)") (class "Default")
      (node (ref "LD11") (pin "3") (pinfunction "BLUE_3") (pintype "bidirectional"))
      (node (ref "R96") (pin "2") (pinfunction "2_2") (pintype "passive"))
    )
    (net (code "147") (name "Net-(LD11-GRN)") (class "Default")
      (node (ref "LD11") (pin "4") (pinfunction "GRN_4") (pintype "bidirectional"))
      (node (ref "R95") (pin "2") (pinfunction "2_2") (pintype "passive"))
    )
    (net (code "148") (name "Net-(LD11-RED)") (class "Default")
      (node (ref "LD11") (pin "1") (pinfunction "RED_1") (pintype "bidirectional"))
      (node (ref "R94") (pin "2") (pinfunction "2_2") (pintype "passive"))
    )
    (net (code "149") (name "Net-(LD12-BLUE)") (class "Default")
      (node (ref "LD12") (pin "3") (pinfunction "BLUE_3") (pintype "bidirectional"))
      (node (ref "R99") (pin "2") (pinfunction "2_2") (pintype "passive"))
    )
    (net (code "150") (name "Net-(LD12-GRN)") (class "Default")
      (node (ref "LD12") (pin "4") (pinfunction "GRN_4") (pintype "bidirectional"))
      (node (ref "R98") (pin "2") (pinfunction "2_2") (pintype "passive"))
    )
    (net (code "151") (name "Net-(LD12-RED)") (class "Default")
      (node (ref "LD12") (pin "1") (pinfunction "RED_1") (pintype "bidirectional"))
      (node (ref "R97") (pin "2") (pinfunction "2_2") (pintype "passive"))
    )
    (net (code "152") (name "Net-(LD13-BLUE)") (class "Default")
      (node (ref "LD13") (pin "3") (pinfunction "BLUE_3") (pintype "bidirectional"))
      (node (ref "R102") (pin "2") (pinfunction "2_2") (pintype "passive"))
    )
    (net (code "153") (name "Net-(LD13-GRN)") (class "Default")
      (node (ref "LD13") (pin "4") (pinfunction "GRN_4") (pintype "bidirectional"))
      (node (ref "R101") (pin "2") (pinfunction "2_2") (pintype "passive"))
    )
    (net (code "154") (name "Net-(LD13-RED)") (class "Default")
      (node (ref "LD13") (pin "1") (pinfunction "RED_1") (pintype "bidirectional"))
      (node (ref "R100") (pin "2") (pinfunction "2_2") (pintype "passive"))
    )
    (net (code "155") (name "Net-(LD14-BLUE)") (class "Default")
      (node (ref "LD14") (pin "3") (pinfunction "BLUE_3") (pintype "bidirectional"))
      (node (ref "R105") (pin "2") (pinfunction "2_2") (pintype "passive"))
    )
    (net (code "156") (name "Net-(LD14-GRN)") (class "Default")
      (node (ref "LD14") (pin "4") (pinfunction "GRN_4") (pintype "bidirectional"))
      (node (ref "R104") (pin "2") (pinfunction "2_2") (pintype "passive"))
    )
    (net (code "157") (name "Net-(LD14-RED)") (class "Default")
      (node (ref "LD14") (pin "1") (pinfunction "RED_1") (pintype "bidirectional"))
      (node (ref "R103") (pin "2") (pinfunction "2_2") (pintype "passive"))
    )
    (net (code "158") (name "Net-(LD15-BLUE)") (class "Default")
      (node (ref "LD15") (pin "3") (pinfunction "BLUE_3") (pintype "bidirectional"))
      (node (ref "R108") (pin "2") (pinfunction "2_2") (pintype "passive"))
    )
    (net (code "159") (name "Net-(LD15-GRN)") (class "Default")
      (node (ref "LD15") (pin "4") (pinfunction "GRN_4") (pintype "bidirectional"))
      (node (ref "R107") (pin "2") (pinfunction "2_2") (pintype "passive"))
    )
    (net (code "160") (name "Net-(LD15-RED)") (class "Default")
      (node (ref "LD15") (pin "1") (pinfunction "RED_1") (pintype "bidirectional"))
      (node (ref "R106") (pin "2") (pinfunction "2_2") (pintype "passive"))
    )
    (net (code "161") (name "Net-(LD16-BLUE)") (class "Default")
      (node (ref "LD16") (pin "3") (pinfunction "BLUE_3") (pintype "bidirectional"))
      (node (ref "R111") (pin "2") (pinfunction "2_2") (pintype "passive"))
    )
    (net (code "162") (name "Net-(LD16-GRN)") (class "Default")
      (node (ref "LD16") (pin "4") (pinfunction "GRN_4") (pintype "bidirectional"))
      (node (ref "R110") (pin "2") (pinfunction "2_2") (pintype "passive"))
    )
    (net (code "163") (name "Net-(LD16-RED)") (class "Default")
      (node (ref "LD16") (pin "1") (pinfunction "RED_1") (pintype "bidirectional"))
      (node (ref "R109") (pin "2") (pinfunction "2_2") (pintype "passive"))
    )
    (net (code "164") (name "Net-(LD17-BLUE)") (class "Default")
      (node (ref "LD17") (pin "3") (pinfunction "BLUE_3") (pintype "bidirectional"))
      (node (ref "R4") (pin "2") (pinfunction "2_2") (pintype "passive"))
    )
    (net (code "165") (name "Net-(LD17-GRN)") (class "Default")
      (node (ref "LD17") (pin "4") (pinfunction "GRN_4") (pintype "bidirectional"))
      (node (ref "R3") (pin "2") (pinfunction "2_2") (pintype "passive"))
    )
    (net (code "166") (name "Net-(LD17-RED)") (class "Default")
      (node (ref "LD17") (pin "1") (pinfunction "RED_1") (pintype "bidirectional"))
      (node (ref "R2") (pin "2") (pinfunction "2_2") (pintype "passive"))
    )
    (net (code "167") (name "Net-(LD18-BLUE)") (class "Default")
      (node (ref "LD18") (pin "3") (pinfunction "BLUE_3") (pintype "bidirectional"))
      (node (ref "R7") (pin "2") (pinfunction "2_2") (pintype "passive"))
    )
    (net (code "168") (name "Net-(LD18-GRN)") (class "Default")
      (node (ref "LD18") (pin "4") (pinfunction "GRN_4") (pintype "bidirectional"))
      (node (ref "R6") (pin "2") (pinfunction "2_2") (pintype "passive"))
    )
    (net (code "169") (name "Net-(LD18-RED)") (class "Default")
      (node (ref "LD18") (pin "1") (pinfunction "RED_1") (pintype "bidirectional"))
      (node (ref "R5") (pin "2") (pinfunction "2_2") (pintype "passive"))
    )
    (net (code "170") (name "Net-(LD19-BLUE)") (class "Default")
      (node (ref "LD19") (pin "3") (pinfunction "BLUE_3") (pintype "bidirectional"))
      (node (ref "R10") (pin "2") (pinfunction "2_2") (pintype "passive"))
    )
    (net (code "171") (name "Net-(LD19-GRN)") (class "Default")
      (node (ref "LD19") (pin "4") (pinfunction "GRN_4") (pintype "bidirectional"))
      (node (ref "R9") (pin "2") (pinfunction "2_2") (pintype "passive"))
    )
    (net (code "172") (name "Net-(LD19-RED)") (class "Default")
      (node (ref "LD19") (pin "1") (pinfunction "RED_1") (pintype "bidirectional"))
      (node (ref "R8") (pin "2") (pinfunction "2_2") (pintype "passive"))
    )
    (net (code "173") (name "Net-(LD20-BLUE)") (class "Default")
      (node (ref "LD20") (pin "3") (pinfunction "BLUE_3") (pintype "bidirectional"))
      (node (ref "R13") (pin "2") (pinfunction "2_2") (pintype "passive"))
    )
    (net (code "174") (name "Net-(LD20-GRN)") (class "Default")
      (node (ref "LD20") (pin "4") (pinfunction "GRN_4") (pintype "bidirectional"))
      (node (ref "R12") (pin "2") (pinfunction "2_2") (pintype "passive"))
    )
    (net (code "175") (name "Net-(LD20-RED)") (class "Default")
      (node (ref "LD20") (pin "1") (pinfunction "RED_1") (pintype "bidirectional"))
      (node (ref "R11") (pin "2") (pinfunction "2_2") (pintype "passive"))
    )
    (net (code "176") (name "Net-(LD21-BLUE)") (class "Default")
      (node (ref "LD21") (pin "3") (pinfunction "BLUE_3") (pintype "bidirectional"))
      (node (ref "R16") (pin "2") (pinfunction "2_2") (pintype "passive"))
    )
    (net (code "177") (name "Net-(LD21-GRN)") (class "Default")
      (node (ref "LD21") (pin "4") (pinfunction "GRN_4") (pintype "bidirectional"))
      (node (ref "R15") (pin "2") (pinfunction "2_2") (pintype "passive"))
    )
    (net (code "178") (name "Net-(LD21-RED)") (class "Default")
      (node (ref "LD21") (pin "1") (pinfunction "RED_1") (pintype "bidirectional"))
      (node (ref "R14") (pin "2") (pinfunction "2_2") (pintype "passive"))
    )
    (net (code "179") (name "Net-(LD22-BLUE)") (class "Default")
      (node (ref "LD22") (pin "3") (pinfunction "BLUE_3") (pintype "bidirectional"))
      (node (ref "R19") (pin "2") (pinfunction "2_2") (pintype "passive"))
    )
    (net (code "180") (name "Net-(LD22-GRN)") (class "Default")
      (node (ref "LD22") (pin "4") (pinfunction "GRN_4") (pintype "bidirectional"))
      (node (ref "R18") (pin "2") (pinfunction "2_2") (pintype "passive"))
    )
    (net (code "181") (name "Net-(LD22-RED)") (class "Default")
      (node (ref "LD22") (pin "1") (pinfunction "RED_1") (pintype "bidirectional"))
      (node (ref "R17") (pin "2") (pinfunction "2_2") (pintype "passive"))
    )
    (net (code "182") (name "Net-(LD23-BLUE)") (class "Default")
      (node (ref "LD23") (pin "3") (pinfunction "BLUE_3") (pintype "bidirectional"))
      (node (ref "R22") (pin "2") (pinfunction "2_2") (pintype "passive"))
    )
    (net (code "183") (name "Net-(LD23-GRN)") (class "Default")
      (node (ref "LD23") (pin "4") (pinfunction "GRN_4") (pintype "bidirectional"))
      (node (ref "R21") (pin "2") (pinfunction "2_2") (pintype "passive"))
    )
    (net (code "184") (name "Net-(LD23-RED)") (class "Default")
      (node (ref "LD23") (pin "1") (pinfunction "RED_1") (pintype "bidirectional"))
      (node (ref "R20") (pin "2") (pinfunction "2_2") (pintype "passive"))
    )
    (net (code "185") (name "Net-(LD24-BLUE)") (class "Default")
      (node (ref "LD24") (pin "3") (pinfunction "BLUE_3") (pintype "bidirectional"))
      (node (ref "R25") (pin "2") (pinfunction "2_2") (pintype "passive"))
    )
    (net (code "186") (name "Net-(LD24-GRN)") (class "Default")
      (node (ref "LD24") (pin "4") (pinfunction "GRN_4") (pintype "bidirectional"))
      (node (ref "R24") (pin "2") (pinfunction "2_2") (pintype "passive"))
    )
    (net (code "187") (name "Net-(LD24-RED)") (class "Default")
      (node (ref "LD24") (pin "1") (pinfunction "RED_1") (pintype "bidirectional"))
      (node (ref "R23") (pin "2") (pinfunction "2_2") (pintype "passive"))
    )
    (net (code "188") (name "Net-(LD25-BLUE)") (class "Default")
      (node (ref "LD25") (pin "3") (pinfunction "BLUE_3") (pintype "bidirectional"))
      (node (ref "R28") (pin "2") (pinfunction "2_2") (pintype "passive"))
    )
    (net (code "189") (name "Net-(LD25-GRN)") (class "Default")
      (node (ref "LD25") (pin "4") (pinfunction "GRN_4") (pintype "bidirectional"))
      (node (ref "R27") (pin "2") (pinfunction "2_2") (pintype "passive"))
    )
    (net (code "190") (name "Net-(LD25-RED)") (class "Default")
      (node (ref "LD25") (pin "1") (pinfunction "RED_1") (pintype "bidirectional"))
      (node (ref "R26") (pin "2") (pinfunction "2_2") (pintype "passive"))
    )
    (net (code "191") (name "Net-(LD26-BLUE)") (class "Default")
      (node (ref "LD26") (pin "3") (pinfunction "BLUE_3") (pintype "bidirectional"))
      (node (ref "R31") (pin "2") (pinfunction "2_2") (pintype "passive"))
    )
    (net (code "192") (name "Net-(LD26-GRN)") (class "Default")
      (node (ref "LD26") (pin "4") (pinfunction "GRN_4") (pintype "bidirectional"))
      (node (ref "R30") (pin "2") (pinfunction "2_2") (pintype "passive"))
    )
    (net (code "193") (name "Net-(LD26-RED)") (class "Default")
      (node (ref "LD26") (pin "1") (pinfunction "RED_1") (pintype "bidirectional"))
      (node (ref "R29") (pin "2") (pinfunction "2_2") (pintype "passive"))
    )
    (net (code "194") (name "Net-(LD27-BLUE)") (class "Default")
      (node (ref "LD27") (pin "3") (pinfunction "BLUE_3") (pintype "bidirectional"))
      (node (ref "R34") (pin "2") (pinfunction "2_2") (pintype "passive"))
    )
    (net (code "195") (name "Net-(LD27-GRN)") (class "Default")
      (node (ref "LD27") (pin "4") (pinfunction "GRN_4") (pintype "bidirectional"))
      (node (ref "R33") (pin "2") (pinfunction "2_2") (pintype "passive"))
    )
    (net (code "196") (name "Net-(LD27-RED)") (class "Default")
      (node (ref "LD27") (pin "1") (pinfunction "RED_1") (pintype "bidirectional"))
      (node (ref "R32") (pin "2") (pinfunction "2_2") (pintype "passive"))
    )
    (net (code "197") (name "Net-(LD28-BLUE)") (class "Default")
      (node (ref "LD28") (pin "3") (pinfunction "BLUE_3") (pintype "bidirectional"))
      (node (ref "R37") (pin "2") (pinfunction "2_2") (pintype "passive"))
    )
    (net (code "198") (name "Net-(LD28-GRN)") (class "Default")
      (node (ref "LD28") (pin "4") (pinfunction "GRN_4") (pintype "bidirectional"))
      (node (ref "R36") (pin "2") (pinfunction "2_2") (pintype "passive"))
    )
    (net (code "199") (name "Net-(LD28-RED)") (class "Default")
      (node (ref "LD28") (pin "1") (pinfunction "RED_1") (pintype "bidirectional"))
      (node (ref "R35") (pin "2") (pinfunction "2_2") (pintype "passive"))
    )
    (net (code "200") (name "Net-(LD29-BLUE)") (class "Default")
      (node (ref "LD29") (pin "3") (pinfunction "BLUE_3") (pintype "bidirectional"))
      (node (ref "R40") (pin "2") (pinfunction "2_2") (pintype "passive"))
    )
    (net (code "201") (name "Net-(LD29-GRN)") (class "Default")
      (node (ref "LD29") (pin "4") (pinfunction "GRN_4") (pintype "bidirectional"))
      (node (ref "R39") (pin "2") (pinfunction "2_2") (pintype "passive"))
    )
    (net (code "202") (name "Net-(LD29-RED)") (class "Default")
      (node (ref "LD29") (pin "1") (pinfunction "RED_1") (pintype "bidirectional"))
      (node (ref "R38") (pin "2") (pinfunction "2_2") (pintype "passive"))
    )
    (net (code "203") (name "Net-(LD30-BLUE)") (class "Default")
      (node (ref "LD30") (pin "3") (pinfunction "BLUE_3") (pintype "bidirectional"))
      (node (ref "R43") (pin "2") (pinfunction "2_2") (pintype "passive"))
    )
    (net (code "204") (name "Net-(LD30-GRN)") (class "Default")
      (node (ref "LD30") (pin "4") (pinfunction "GRN_4") (pintype "bidirectional"))
      (node (ref "R42") (pin "2") (pinfunction "2_2") (pintype "passive"))
    )
    (net (code "205") (name "Net-(LD30-RED)") (class "Default")
      (node (ref "LD30") (pin "1") (pinfunction "RED_1") (pintype "bidirectional"))
      (node (ref "R41") (pin "2") (pinfunction "2_2") (pintype "passive"))
    )
    (net (code "206") (name "Net-(LD31-BLUE)") (class "Default")
      (node (ref "LD31") (pin "3") (pinfunction "BLUE_3") (pintype "bidirectional"))
      (node (ref "R46") (pin "2") (pinfunction "2_2") (pintype "passive"))
    )
    (net (code "207") (name "Net-(LD31-GRN)") (class "Default")
      (node (ref "LD31") (pin "4") (pinfunction "GRN_4") (pintype "bidirectional"))
      (node (ref "R45") (pin "2") (pinfunction "2_2") (pintype "passive"))
    )
    (net (code "208") (name "Net-(LD31-RED)") (class "Default")
      (node (ref "LD31") (pin "1") (pinfunction "RED_1") (pintype "bidirectional"))
      (node (ref "R44") (pin "2") (pinfunction "2_2") (pintype "passive"))
    )
    (net (code "209") (name "Net-(LD32-BLUE)") (class "Default")
      (node (ref "LD32") (pin "3") (pinfunction "BLUE_3") (pintype "bidirectional"))
      (node (ref "R56") (pin "2") (pinfunction "2_2") (pintype "passive"))
    )
    (net (code "210") (name "Net-(LD32-GRN)") (class "Default")
      (node (ref "LD32") (pin "4") (pinfunction "GRN_4") (pintype "bidirectional"))
      (node (ref "R48") (pin "2") (pinfunction "2_2") (pintype "passive"))
    )
    (net (code "211") (name "Net-(LD32-RED)") (class "Default")
      (node (ref "LD32") (pin "1") (pinfunction "RED_1") (pintype "bidirectional"))
      (node (ref "R47") (pin "2") (pinfunction "2_2") (pintype "passive"))
    )
    (net (code "212") (name "Net-(LD33-BLUE)") (class "Default")
      (node (ref "LD33") (pin "3") (pinfunction "BLUE_3") (pintype "bidirectional"))
      (node (ref "R115") (pin "2") (pinfunction "2_2") (pintype "passive"))
    )
    (net (code "213") (name "Net-(LD33-GRN)") (class "Default")
      (node (ref "LD33") (pin "4") (pinfunction "GRN_4") (pintype "bidirectional"))
      (node (ref "R114") (pin "2") (pinfunction "2_2") (pintype "passive"))
    )
    (net (code "214") (name "Net-(LD33-RED)") (class "Default")
      (node (ref "LD33") (pin "1") (pinfunction "RED_1") (pintype "bidirectional"))
      (node (ref "R58") (pin "2") (pinfunction "2_2") (pintype "passive"))
    )
    (net (code "215") (name "Net-(Q1-1)") (class "Default")
      (node (ref "C10") (pin "2") (pinfunction "2_2") (pintype "passive"))
      (node (ref "Q1") (pin "P$1") (pinfunction "1_P$1") (pintype "passive"))
      (node (ref "U1") (pin "15") (pinfunction "EXTAL32_15") (pintype "passive"))
    )
    (net (code "216") (name "Net-(Q1-2)") (class "Default")
      (node (ref "C9") (pin "2") (pinfunction "2_2") (pintype "passive"))
      (node (ref "Q1") (pin "P$2") (pinfunction "2_P$2") (pintype "passive"))
      (node (ref "U1") (pin "14") (pinfunction "XTAL32_14") (pintype "passive"))
    )
    (net (code "217") (name "Net-(R50-Pad1)") (class "Default")
      (node (ref "R50") (pin "1") (pinfunction "1_1") (pintype "passive"))
      (node (ref "X4") (pin "1") (pinfunction "1_1") (pintype "input"))
    )
    (net (code "218") (name "Net-(U1-PTA18)") (class "Default")
      (node (ref "C12") (pin "2") (pinfunction "2_2") (pintype "passive"))
      (node (ref "Q2") (pin "3") (pinfunction "3_3") (pintype "passive"))
      (node (ref "R1") (pin "2") (pinfunction "2_2") (pintype "passive"))
      (node (ref "U1") (pin "24") (pinfunction "PTA18_24") (pintype "bidirectional"))
    )
    (net (code "219") (name "Net-(U1-PTA19)") (class "Default")
      (node (ref "C13") (pin "2") (pinfunction "2_2") (pintype "passive"))
      (node (ref "Q2") (pin "1") (pinfunction "1_1") (pintype "passive"))
      (node (ref "R1") (pin "1") (pinfunction "1_1") (pintype "passive"))
      (node (ref "U1") (pin "25") (pinfunction "PTA19_25") (pintype "bidirectional"))
    )
    (net (code "220") (name "Net-(U2-CAP)") (class "Default")
      (node (ref "C8") (pin "1") (pinfunction "1_1") (pintype "passive"))
      (node (ref "U2") (pin "2") (pinfunction "CAP_2") (pintype "passive"))
    )
    (net (code "221") (name "Net-(U3-BYP)") (class "Default")
      (node (ref "C28") (pin "1") (pinfunction "1_1") (pintype "passive"))
      (node (ref "U3") (pin "2") (pinfunction "BYP_2") (pintype "input"))
    )
    (net (code "222") (name "Net-(U4-PROG)") (class "Default")
      (node (ref "R51") (pin "2") (pinfunction "2_2") (pintype "passive"))
      (node (ref "U4") (pin "5") (pinfunction "PROG_5") (pintype "input"))
    )
    (net (code "223") (name "Net-(X4A-S1)") (class "Default")
      (node (ref "R63") (pin "2") (pinfunction "2_2") (pintype "passive"))
      (node (ref "X4") (pin "M1") (pinfunction "S1_M1") (pintype "passive"))
      (node (ref "X4") (pin "M2") (pinfunction "S2_M2") (pintype "passive"))
      (node (ref "X4") (pin "M3") (pinfunction "S3_M3") (pintype "passive"))
      (node (ref "X4") (pin "M4") (pinfunction "S4_M4") (pintype "passive"))
    )
    (net (code "224") (name "Q1B") (class "Default")
      (node (ref "U16") (pin "14") (pinfunction "A_14") (pintype "input"))
      (node (ref "U17") (pin "9") (pinfunction "SQH_9") (pintype "bidirectional"))
    )
    (net (code "225") (name "Q1T") (class "Default")
      (node (ref "U10") (pin "14") (pinfunction "A_14") (pintype "input"))
      (node (ref "U11") (pin "9") (pinfunction "SQH_9") (pintype "bidirectional"))
    )
    (net (code "226") (name "Q2B") (class "Default")
      (node (ref "U15") (pin "14") (pinfunction "A_14") (pintype "input"))
      (node (ref "U16") (pin "9") (pinfunction "SQH_9") (pintype "bidirectional"))
    )
    (net (code "227") (name "Q2T") (class "Default")
      (node (ref "U10") (pin "9") (pinfunction "SQH_9") (pintype "bidirectional"))
      (node (ref "U9") (pin "14") (pinfunction "A_14") (pintype "input"))
    )
    (net (code "228") (name "Q3B") (class "Default")
      (node (ref "U14") (pin "14") (pinfunction "A_14") (pintype "input"))
      (node (ref "U15") (pin "9") (pinfunction "SQH_9") (pintype "bidirectional"))
    )
    (net (code "229") (name "Q3T") (class "Default")
      (node (ref "U8") (pin "14") (pinfunction "A_14") (pintype "input"))
      (node (ref "U9") (pin "9") (pinfunction "SQH_9") (pintype "bidirectional"))
    )
    (net (code "230") (name "Q4B") (class "Default")
      (node (ref "U13") (pin "14") (pinfunction "A_14") (pintype "input"))
      (node (ref "U14") (pin "9") (pinfunction "SQH_9") (pintype "bidirectional"))
    )
    (net (code "231") (name "Q4T") (class "Default")
      (node (ref "U7") (pin "14") (pinfunction "A_14") (pintype "input"))
      (node (ref "U8") (pin "9") (pinfunction "SQH_9") (pintype "bidirectional"))
    )
    (net (code "232") (name "Q5B") (class "Default")
      (node (ref "U12") (pin "14") (pinfunction "A_14") (pintype "input"))
      (node (ref "U13") (pin "9") (pinfunction "SQH_9") (pintype "bidirectional"))
    )
    (net (code "233") (name "Q5T") (class "Default")
      (node (ref "U6") (pin "14") (pinfunction "A_14") (pintype "input"))
      (node (ref "U7") (pin "9") (pinfunction "SQH_9") (pintype "bidirectional"))
    )
    (net (code "234") (name "RESET") (class "Default")
      (node (ref "C11") (pin "1") (pinfunction "1_1") (pintype "passive"))
      (node (ref "R57") (pin "1") (pinfunction "1_1") (pintype "passive"))
      (node (ref "U1") (pin "26") (pinfunction "RESET_B_26") (pintype "passive"))
      (node (ref "X1") (pin "P$10") (pinfunction "10_P$10") (pintype "passive"))
    )
    (net (code "235") (name "SPI-CK") (class "Default")
      (node (ref "U1") (pin "38") (pinfunction "PTC5/LLWU_P9_38") (pintype "bidirectional"))
      (node (ref "U10") (pin "11") (pinfunction "SHIFT_CLOCK_11") (pintype "input"))
      (node (ref "U11") (pin "11") (pinfunction "SHIFT_CLOCK_11") (pintype "input"))
      (node (ref "U12") (pin "11") (pinfunction "SHIFT_CLOCK_11") (pintype "input"))
      (node (ref "U13") (pin "11") (pinfunction "SHIFT_CLOCK_11") (pintype "input"))
      (node (ref "U14") (pin "11") (pinfunction "SHIFT_CLOCK_11") (pintype "input"))
      (node (ref "U15") (pin "11") (pinfunction "SHIFT_CLOCK_11") (pintype "input"))
      (node (ref "U16") (pin "11") (pinfunction "SHIFT_CLOCK_11") (pintype "input"))
      (node (ref "U17") (pin "11") (pinfunction "SHIFT_CLOCK_11") (pintype "input"))
      (node (ref "U6") (pin "11") (pinfunction "SHIFT_CLOCK_11") (pintype "input"))
      (node (ref "U7") (pin "11") (pinfunction "SHIFT_CLOCK_11") (pintype "input"))
      (node (ref "U8") (pin "11") (pinfunction "SHIFT_CLOCK_11") (pintype "input"))
      (node (ref "U9") (pin "11") (pinfunction "SHIFT_CLOCK_11") (pintype "input"))
      (node (ref "X5") (pin "5") (pinfunction "5_5") (pintype "passive"))
      (node (ref "X6") (pin "5") (pinfunction "5_5") (pintype "passive"))
    )
    (net (code "236") (name "SPI-OE") (class "Default")
      (node (ref "U1") (pin "21") (pinfunction "PTA4/LLWU_P3_21") (pintype "bidirectional"))
      (node (ref "U10") (pin "13") (pinfunction "OUTPUT_ENABLE_13") (pintype "input"))
      (node (ref "U11") (pin "13") (pinfunction "OUTPUT_ENABLE_13") (pintype "input"))
      (node (ref "U12") (pin "13") (pinfunction "OUTPUT_ENABLE_13") (pintype "input"))
      (node (ref "U13") (pin "13") (pinfunction "OUTPUT_ENABLE_13") (pintype "input"))
      (node (ref "U14") (pin "13") (pinfunction "OUTPUT_ENABLE_13") (pintype "input"))
      (node (ref "U15") (pin "13") (pinfunction "OUTPUT_ENABLE_13") (pintype "input"))
      (node (ref "U16") (pin "13") (pinfunction "OUTPUT_ENABLE_13") (pintype "input"))
      (node (ref "U17") (pin "13") (pinfunction "OUTPUT_ENABLE_13") (pintype "input"))
      (node (ref "U6") (pin "13") (pinfunction "OUTPUT_ENABLE_13") (pintype "input"))
      (node (ref "U7") (pin "13") (pinfunction "OUTPUT_ENABLE_13") (pintype "input"))
      (node (ref "U8") (pin "13") (pinfunction "OUTPUT_ENABLE_13") (pintype "input"))
      (node (ref "U9") (pin "13") (pinfunction "OUTPUT_ENABLE_13") (pintype "input"))
      (node (ref "X5") (pin "1") (pinfunction "1_1") (pintype "passive"))
      (node (ref "X6") (pin "1") (pinfunction "1_1") (pintype "passive"))
    )
    (net (code "237") (name "SPI-OUT") (class "Default")
      (node (ref "U1") (pin "39") (pinfunction "PTC6/LLWU_P10_39") (pintype "bidirectional"))
      (node (ref "U11") (pin "14") (pinfunction "A_14") (pintype "input"))
      (node (ref "U17") (pin "14") (pinfunction "A_14") (pintype "input"))
      (node (ref "X5") (pin "6") (pinfunction "6_6") (pintype "passive"))
      (node (ref "X6") (pin "6") (pinfunction "6_6") (pintype "passive"))
    )
    (net (code "238") (name "SPI-R") (class "Default")
      (node (ref "U1") (pin "37") (pinfunction "PTC4/LLWU_P8_37") (pintype "bidirectional"))
      (node (ref "U10") (pin "10") (pinfunction "RESET_10") (pintype "input"))
      (node (ref "U11") (pin "10") (pinfunction "RESET_10") (pintype "input"))
      (node (ref "U12") (pin "10") (pinfunction "RESET_10") (pintype "input"))
      (node (ref "U13") (pin "10") (pinfunction "RESET_10") (pintype "input"))
      (node (ref "U14") (pin "10") (pinfunction "RESET_10") (pintype "input"))
      (node (ref "U15") (pin "10") (pinfunction "RESET_10") (pintype "input"))
      (node (ref "U16") (pin "10") (pinfunction "RESET_10") (pintype "input"))
      (node (ref "U17") (pin "10") (pinfunction "RESET_10") (pintype "input"))
      (node (ref "U6") (pin "10") (pinfunction "RESET_10") (pintype "input"))
      (node (ref "U7") (pin "10") (pinfunction "RESET_10") (pintype "input"))
      (node (ref "U8") (pin "10") (pinfunction "RESET_10") (pintype "input"))
      (node (ref "U9") (pin "10") (pinfunction "RESET_10") (pintype "input"))
      (node (ref "X5") (pin "4") (pinfunction "4_4") (pintype "passive"))
      (node (ref "X6") (pin "4") (pinfunction "4_4") (pintype "passive"))
    )
    (net (code "239") (name "SPI-STB") (class "Default")
      (node (ref "U1") (pin "36") (pinfunction "PTC3/LLWU_P7_36") (pintype "bidirectional"))
      (node (ref "U12") (pin "12") (pinfunction "LATCH_CLOCK_12") (pintype "input"))
      (node (ref "U13") (pin "12") (pinfunction "LATCH_CLOCK_12") (pintype "input"))
      (node (ref "U14") (pin "12") (pinfunction "LATCH_CLOCK_12") (pintype "input"))
      (node (ref "U15") (pin "12") (pinfunction "LATCH_CLOCK_12") (pintype "input"))
      (node (ref "U16") (pin "12") (pinfunction "LATCH_CLOCK_12") (pintype "input"))
      (node (ref "U17") (pin "12") (pinfunction "LATCH_CLOCK_12") (pintype "input"))
      (node (ref "X5") (pin "3") (pinfunction "3_3") (pintype "passive"))
      (node (ref "X6") (pin "3") (pinfunction "3_3") (pintype "passive"))
    )
    (net (code "240") (name "SPI-STT") (class "Default")
      (node (ref "U1") (pin "35") (pinfunction "PTC2_35") (pintype "bidirectional"))
      (node (ref "U10") (pin "12") (pinfunction "LATCH_CLOCK_12") (pintype "input"))
      (node (ref "U11") (pin "12") (pinfunction "LATCH_CLOCK_12") (pintype "input"))
      (node (ref "U6") (pin "12") (pinfunction "LATCH_CLOCK_12") (pintype "input"))
      (node (ref "U7") (pin "12") (pinfunction "LATCH_CLOCK_12") (pintype "input"))
      (node (ref "U8") (pin "12") (pinfunction "LATCH_CLOCK_12") (pintype "input"))
      (node (ref "U9") (pin "12") (pinfunction "LATCH_CLOCK_12") (pintype "input"))
      (node (ref "X5") (pin "2") (pinfunction "2_2") (pintype "passive"))
      (node (ref "X6") (pin "2") (pinfunction "2_2") (pintype "passive"))
    )
    (net (code "241") (name "SWD-CLK") (class "Default")
      (node (ref "U1") (pin "17") (pinfunction "PTA0_17") (pintype "bidirectional"))
      (node (ref "X1") (pin "P$4") (pinfunction "4_P$4") (pintype "passive"))
    )
    (net (code "242") (name "SWD-DIO") (class "Default")
      (node (ref "U1") (pin "20") (pinfunction "PTA3_20") (pintype "bidirectional"))
      (node (ref "X1") (pin "P$2") (pinfunction "2_P$2") (pintype "passive"))
    )
    (net (code "243") (name "UART-CTS-M") (class "Default")
      (node (ref "U1") (pin "30") (pinfunction "PTB3_30") (pintype "bidirectional"))
      (node (ref "U5") (pin "20") (pinfunction "SIO_05/AIN3/RTS_20") (pintype "bidirectional"))
    )
    (net (code "244") (name "UART-RTS-M") (class "Default")
      (node (ref "U1") (pin "29") (pinfunction "PTB2_29") (pintype "bidirectional"))
      (node (ref "U5") (pin "18") (pinfunction "SIO_07/CTS_18") (pintype "bidirectional"))
    )
    (net (code "245") (name "UART-RX") (class "Default")
      (node (ref "U1") (pin "31") (pinfunction "PTB16_31") (pintype "bidirectional"))
      (node (ref "U5") (pin "19") (pinfunction "SIO_06/TX_19") (pintype "bidirectional"))
    )
    (net (code "246") (name "UART-TX") (class "Default")
      (node (ref "U1") (pin "32") (pinfunction "PTB17_32") (pintype "bidirectional"))
      (node (ref "U5") (pin "17") (pinfunction "SIO_08/RX_17") (pintype "bidirectional"))
    )
    (net (code "247") (name "USB-DN") (class "Default")
      (node (ref "R54") (pin "2") (pinfunction "2_2") (pintype "passive"))
      (node (ref "U1") (pin "4") (pinfunction "USB0_DM_4") (pintype "passive"))
    )
    (net (code "248") (name "USB-DP") (class "Default")
      (node (ref "R55") (pin "2") (pinfunction "2_2") (pintype "passive"))
      (node (ref "U1") (pin "3") (pinfunction "USB0_DP_3") (pintype "passive"))
    )
    (net (code "249") (name "USB-SUPPLY") (class "Default")
      (node (ref "R59") (pin "1") (pinfunction "1_1") (pintype "passive"))
      (node (ref "R60") (pin "1") (pinfunction "1_1") (pintype "passive"))
      (node (ref "U1") (pin "46") (pinfunction "PTD5_46") (pintype "bidirectional"))
    )
    (net (code "250") (name "V+") (class "Default")
      (node (ref "C15") (pin "1") (pinfunction "1_1") (pintype "passive"))
      (node (ref "C18") (pin "1") (pinfunction "1_1") (pintype "passive"))
      (node (ref "C21") (pin "1") (pinfunction "1_1") (pintype "passive"))
      (node (ref "C26") (pin "1") (pinfunction "1_1") (pintype "passive"))
      (node (ref "C3") (pin "1") (pinfunction "1_1") (pintype "passive"))
      (node (ref "C4") (pin "1") (pinfunction "1_1") (pintype "passive"))
      (node (ref "C5") (pin "1") (pinfunction "1_1") (pintype "passive"))
      (node (ref "D4") (pin "3") (pinfunction "CC_3") (pintype "passive"))
      (node (ref "LD1") (pin "2") (pinfunction "ANODE_2") (pintype "power_in"))
      (node (ref "LD10") (pin "2") (pinfunction "ANODE_2") (pintype "power_in"))
      (node (ref "LD11") (pin "2") (pinfunction "ANODE_2") (pintype "power_in"))
      (node (ref "LD12") (pin "2") (pinfunction "ANODE_2") (pintype "power_in"))
      (node (ref "LD13") (pin "2") (pinfunction "ANODE_2") (pintype "power_in"))
      (node (ref "LD14") (pin "2") (pinfunction "ANODE_2") (pintype "power_in"))
      (node (ref "LD15") (pin "2") (pinfunction "ANODE_2") (pintype "power_in"))
      (node (ref "LD16") (pin "2") (pinfunction "ANODE_2") (pintype "power_in"))
      (node (ref "LD17") (pin "2") (pinfunction "ANODE_2") (pintype "power_in"))
      (node (ref "LD18") (pin "2") (pinfunction "ANODE_2") (pintype "power_in"))
      (node (ref "LD19") (pin "2") (pinfunction "ANODE_2") (pintype "power_in"))
      (node (ref "LD2") (pin "2") (pinfunction "ANODE_2") (pintype "power_in"))
      (node (ref "LD20") (pin "2") (pinfunction "ANODE_2") (pintype "power_in"))
      (node (ref "LD21") (pin "2") (pinfunction "ANODE_2") (pintype "power_in"))
      (node (ref "LD22") (pin "2") (pinfunction "ANODE_2") (pintype "power_in"))
      (node (ref "LD23") (pin "2") (pinfunction "ANODE_2") (pintype "power_in"))
      (node (ref "LD24") (pin "2") (pinfunction "ANODE_2") (pintype "power_in"))
      (node (ref "LD25") (pin "2") (pinfunction "ANODE_2") (pintype "power_in"))
      (node (ref "LD26") (pin "2") (pinfunction "ANODE_2") (pintype "power_in"))
      (node (ref "LD27") (pin "2") (pinfunction "ANODE_2") (pintype "power_in"))
      (node (ref "LD28") (pin "2") (pinfunction "ANODE_2") (pintype "power_in"))
      (node (ref "LD29") (pin "2") (pinfunction "ANODE_2") (pintype "power_in"))
      (node (ref "LD3") (pin "2") (pinfunction "ANODE_2") (pintype "power_in"))
      (node (ref "LD30") (pin "2") (pinfunction "ANODE_2") (pintype "power_in"))
      (node (ref "LD31") (pin "2") (pinfunction "ANODE_2") (pintype "power_in"))
      (node (ref "LD32") (pin "2") (pinfunction "ANODE_2") (pintype "power_in"))
      (node (ref "LD4") (pin "2") (pinfunction "ANODE_2") (pintype "power_in"))
      (node (ref "LD5") (pin "2") (pinfunction "ANODE_2") (pintype "power_in"))
      (node (ref "LD6") (pin "2") (pinfunction "ANODE_2") (pintype "power_in"))
      (node (ref "LD7") (pin "2") (pinfunction "ANODE_2") (pintype "power_in"))
      (node (ref "LD8") (pin "2") (pinfunction "ANODE_2") (pintype "power_in"))
      (node (ref "LD9") (pin "2") (pinfunction "ANODE_2") (pintype "power_in"))
      (node (ref "U1") (pin "6") (pinfunction "VREGIN_6") (pintype "input"))
      (node (ref "U10") (pin "16") (pinfunction "VCC_16") (pintype "power_in"))
      (node (ref "U11") (pin "16") (pinfunction "VCC_16") (pintype "power_in"))
      (node (ref "U12") (pin "16") (pinfunction "VCC_16") (pintype "power_in"))
      (node (ref "U13") (pin "16") (pinfunction "VCC_16") (pintype "power_in"))
      (node (ref "U14") (pin "16") (pinfunction "VCC_16") (pintype "power_in"))
      (node (ref "U15") (pin "16") (pinfunction "VCC_16") (pintype "power_in"))
      (node (ref "U16") (pin "16") (pinfunction "VCC_16") (pintype "power_in"))
      (node (ref "U17") (pin "16") (pinfunction "VCC_16") (pintype "power_in"))
      (node (ref "U6") (pin "16") (pinfunction "VCC_16") (pintype "power_in"))
      (node (ref "U7") (pin "16") (pinfunction "VCC_16") (pintype "power_in"))
      (node (ref "U8") (pin "16") (pinfunction "VCC_16") (pintype "power_in"))
      (node (ref "U9") (pin "16") (pinfunction "VCC_16") (pintype "power_in"))
      (node (ref "X3") (pin "2") (pinfunction "2_2") (pintype "passive"))
      (node (ref "X5") (pin "7") (pinfunction "7_7") (pintype "passive"))
      (node (ref "X6") (pin "7") (pinfunction "7_7") (pintype "passive"))
    )
    (net (code "251") (name "VA-DIS") (class "Default")
      (node (ref "C20") (pin "2") (pinfunction "2_2") (pintype "passive"))
      (node (ref "R113") (pin "1") (pinfunction "1_1") (pintype "passive"))
      (node (ref "U1") (pin "42") (pinfunction "PTD1_42") (pintype "bidirectional"))
    )
    (net (code "252") (name "VACCU") (class "Default")
      (node (ref "C20") (pin "1") (pinfunction "1_1") (pintype "passive"))
      (node (ref "R112") (pin "1") (pinfunction "1_1") (pintype "passive"))
      (node (ref "R113") (pin "2") (pinfunction "2_2") (pintype "passive"))
      (node (ref "U1") (pin "7") (pinfunction "ADC0_DP0_7") (pintype "passive"))
    )
    (net (code "253") (name "VBAT") (class "Default")
      (node (ref "C1") (pin "1") (pinfunction "1_1") (pintype "passive"))
      (node (ref "D2") (pin "1") (pinfunction "K1_1") (pintype "passive"))
      (node (ref "D2") (pin "2") (pinfunction "K2_2") (pintype "passive"))
      (node (ref "D4") (pin "2") (pinfunction "A2_2") (pintype "passive"))
      (node (ref "R112") (pin "2") (pinfunction "2_2") (pintype "passive"))
      (node (ref "U4") (pin "3") (pinfunction "VBAT_3") (pintype "output"))
      (node (ref "X3") (pin "3") (pinfunction "3_3") (pintype "passive"))
    )
    (net (code "254") (name "VBAT-RTC") (class "Default")
      (node (ref "C23") (pin "1") (pinfunction "1_1") (pintype "passive"))
      (node (ref "D3") (pin "3") (pinfunction "CC_3") (pintype "passive"))
      (node (ref "U1") (pin "16") (pinfunction "VBAT_16") (pintype "passive"))
    )
    (net (code "255") (name "VREF") (class "Default")
      (node (ref "C22") (pin "1") (pinfunction "1_1") (pintype "passive"))
      (node (ref "C24") (pin "1") (pinfunction "1_1") (pintype "passive"))
      (node (ref "U1") (pin "10") (pinfunction "VREFH_10") (pintype "passive"))
      (node (ref "U1") (pin "13") (pinfunction "VREF_OUT/CMP1_IN5/CMP0_IN5_13") (pintype "passive"))
    )
    (net (code "256") (name "unconnected-(D3-A2-Pad2)") (class "Default")
      (node (ref "D3") (pin "2") (pinfunction "A2_2") (pintype "passive"))
    )
    (net (code "257") (name "unconnected-(U1-ADC0_DM0-Pad8)") (class "Default")
      (node (ref "U1") (pin "8") (pinfunction "ADC0_DM0_8") (pintype "passive"))
    )
    (net (code "258") (name "unconnected-(U1-PTA2-Pad19)") (class "Default")
      (node (ref "U1") (pin "19") (pinfunction "PTA2_19") (pintype "bidirectional"))
    )
    (net (code "259") (name "unconnected-(U2-INT1-Pad6)") (class "Default")
      (node (ref "U2") (pin "6") (pinfunction "INT1_6") (pintype "passive"))
    )
    (net (code "260") (name "unconnected-(U2-INT2-Pad5)") (class "Default")
      (node (ref "U2") (pin "5") (pinfunction "INT2_5") (pintype "passive"))
    )
    (net (code "261") (name "unconnected-(U3-INT2-Pad9)") (class "Default")
      (node (ref "U3") (pin "9") (pinfunction "INT2_9") (pintype "output"))
    )
    (net (code "262") (name "unconnected-(U3-NC-Pad16)") (class "Default")
      (node (ref "U3") (pin "16") (pinfunction "NC_16") (pintype "no_connect"))
    )
    (net (code "263") (name "unconnected-(U3-NC_2-Pad3)") (class "Default")
      (node (ref "U3") (pin "3") (pinfunction "NC_2_3") (pintype "no_connect"))
    )
    (net (code "264") (name "unconnected-(U3-NC_3-Pad13)") (class "Default")
      (node (ref "U3") (pin "13") (pinfunction "NC_3_13") (pintype "no_connect"))
    )
    (net (code "265") (name "unconnected-(U3-NC_4-Pad15)") (class "Default")
      (node (ref "U3") (pin "15") (pinfunction "NC_4_15") (pintype "no_connect"))
    )
    (net (code "266") (name "unconnected-(U3-NC_5-Pad8)") (class "Default")
      (node (ref "U3") (pin "8") (pinfunction "NC_5_8") (pintype "no_connect"))
    )
    (net (code "267") (name "unconnected-(U5-AIN4{slash}SIO_28-Pad35)") (class "Default")
      (node (ref "U5") (pin "35") (pinfunction "AIN4/SIO_28_35") (pintype "bidirectional"))
    )
    (net (code "268") (name "unconnected-(U5-AIN5{slash}SIO_29-Pad34)") (class "Default")
      (node (ref "U5") (pin "34") (pinfunction "AIN5/SIO_29_34") (pintype "bidirectional"))
    )
    (net (code "269") (name "unconnected-(U5-AIN6{slash}SIO_30-Pad33)") (class "Default")
      (node (ref "U5") (pin "33") (pinfunction "AIN6/SIO_30_33") (pintype "bidirectional"))
    )
    (net (code "270") (name "unconnected-(U5-AIN7{slash}SIO_31-Pad32)") (class "Default")
      (node (ref "U5") (pin "32") (pinfunction "AIN7/SIO_31_32") (pintype "bidirectional"))
    )
    (net (code "271") (name "unconnected-(U5-SIO_00{slash}XL1-Pad25)") (class "Default")
      (node (ref "U5") (pin "25") (pinfunction "SIO_00/XL1_25") (pintype "bidirectional"))
    )
    (net (code "272") (name "unconnected-(U5-SIO_01{slash}XL2-Pad24)") (class "Default")
      (node (ref "U5") (pin "24") (pinfunction "SIO_01/XL2_24") (pintype "bidirectional"))
    )
    (net (code "273") (name "unconnected-(U5-SIO_02{slash}AIN0-Pad23)") (class "Default")
      (node (ref "U5") (pin "23") (pinfunction "SIO_02/AIN0_23") (pintype "bidirectional"))
    )
    (net (code "274") (name "unconnected-(U5-SIO_03{slash}AIN1-Pad22)") (class "Default")
      (node (ref "U5") (pin "22") (pinfunction "SIO_03/AIN1_22") (pintype "bidirectional"))
    )
    (net (code "275") (name "unconnected-(U5-SIO_04{slash}AIN2-Pad21)") (class "Default")
      (node (ref "U5") (pin "21") (pinfunction "SIO_04/AIN2_21") (pintype "bidirectional"))
    )
    (net (code "276") (name "unconnected-(U5-SIO_09{slash}NFC1-Pad15)") (class "Default")
      (node (ref "U5") (pin "15") (pinfunction "SIO_09/NFC1_15") (pintype "bidirectional"))
    )
    (net (code "277") (name "unconnected-(U5-SIO_10{slash}NFC2-Pad14)") (class "Default")
      (node (ref "U5") (pin "14") (pinfunction "SIO_10/NFC2_14") (pintype "bidirectional"))
    )
    (net (code "278") (name "unconnected-(U5-SIO_11-Pad13)") (class "Default")
      (node (ref "U5") (pin "13") (pinfunction "SIO_11_13") (pintype "bidirectional"))
    )
    (net (code "279") (name "unconnected-(U5-SIO_12-Pad12)") (class "Default")
      (node (ref "U5") (pin "12") (pinfunction "SIO_12_12") (pintype "bidirectional"))
    )
    (net (code "280") (name "unconnected-(U5-SIO_14-Pad11)") (class "Default")
      (node (ref "U5") (pin "11") (pinfunction "SIO_14_11") (pintype "bidirectional"))
    )
    (net (code "281") (name "unconnected-(U5-SIO_15-Pad29)") (class "Default")
      (node (ref "U5") (pin "29") (pinfunction "SIO_15_29") (pintype "bidirectional"))
    )
    (net (code "282") (name "unconnected-(U5-SIO_16-Pad10)") (class "Default")
      (node (ref "U5") (pin "10") (pinfunction "SIO_16_10") (pintype "bidirectional"))
    )
    (net (code "283") (name "unconnected-(U5-SIO_17-Pad30)") (class "Default")
      (node (ref "U5") (pin "30") (pinfunction "SIO_17_30") (pintype "bidirectional"))
    )
    (net (code "284") (name "unconnected-(U5-SIO_18-Pad9)") (class "Default")
      (node (ref "U5") (pin "9") (pinfunction "SIO_18_9") (pintype "bidirectional"))
    )
    (net (code "285") (name "unconnected-(U5-SIO_19-Pad31)") (class "Default")
      (node (ref "U5") (pin "31") (pinfunction "SIO_19_31") (pintype "bidirectional"))
    )
    (net (code "286") (name "unconnected-(U5-SIO_20-Pad8)") (class "Default")
      (node (ref "U5") (pin "8") (pinfunction "SIO_20_8") (pintype "bidirectional"))
    )
    (net (code "287") (name "unconnected-(U5-SIO_22-Pad4)") (class "Default")
      (node (ref "U5") (pin "4") (pinfunction "SIO_22_4") (pintype "bidirectional"))
    )
    (net (code "288") (name "unconnected-(U5-SPI_MISO{slash}SIO_24-Pad2)") (class "Default")
      (node (ref "U5") (pin "2") (pinfunction "SPI_MISO/SIO_24_2") (pintype "bidirectional"))
    )
    (net (code "289") (name "unconnected-(U5-SPI_MOSI{slash}SIO_23-Pad3)") (class "Default")
      (node (ref "U5") (pin "3") (pinfunction "SPI_MOSI/SIO_23_3") (pintype "bidirectional"))
    )
    (net (code "290") (name "unconnected-(U6-SQH-Pad9)") (class "Default")
      (node (ref "U6") (pin "9") (pinfunction "SQH_9") (pintype "bidirectional"))
    )
    (net (code "291") (name "unconnected-(U12-SQH-Pad9)") (class "Default")
      (node (ref "U12") (pin "9") (pinfunction "SQH_9") (pintype "bidirectional"))
    )
    (net (code "292") (name "unconnected-(X1-6-PadP$6)") (class "Default")
      (node (ref "X1") (pin "P$6") (pinfunction "6_P$6") (pintype "passive"))
    )
    (net (code "293") (name "unconnected-(X1-7-PadP$7)") (class "Default")
      (node (ref "X1") (pin "P$7") (pinfunction "7_P$7") (pintype "passive"))
    )
    (net (code "294") (name "unconnected-(X1-8-PadP$8)") (class "Default")
      (node (ref "X1") (pin "P$8") (pinfunction "8_P$8") (pintype "passive"))
    )
    (net (code "295") (name "unconnected-(X1-9-PadP$9)") (class "Default")
      (node (ref "X1") (pin "P$9") (pinfunction "9_P$9") (pintype "passive"))
    )
    (net (code "296") (name "unconnected-(X2-6-PadP$6)") (class "Default")
      (node (ref "X2") (pin "P$6") (pinfunction "6_P$6") (pintype "passive"))
    )
    (net (code "297") (name "unconnected-(X2-7-PadP$7)") (class "Default")
      (node (ref "X2") (pin "P$7") (pinfunction "7_P$7") (pintype "passive"))
    )
    (net (code "298") (name "unconnected-(X2-8-PadP$8)") (class "Default")
      (node (ref "X2") (pin "P$8") (pinfunction "8_P$8") (pintype "passive"))
    )
    (net (code "299") (name "unconnected-(X2-9-PadP$9)") (class "Default")
      (node (ref "X2") (pin "P$9") (pinfunction "9_P$9") (pintype "passive"))
    )
    (net (code "300") (name "unconnected-(X4-Pad4)") (class "Default")
      (node (ref "X4") (pin "4") (pinfunction "4_4") (pintype "input"))
    )
  )
)
